# ife19_TS_BMS_v2_Eagle.net
KiCad netlist of a schematic drawn in EAGLE
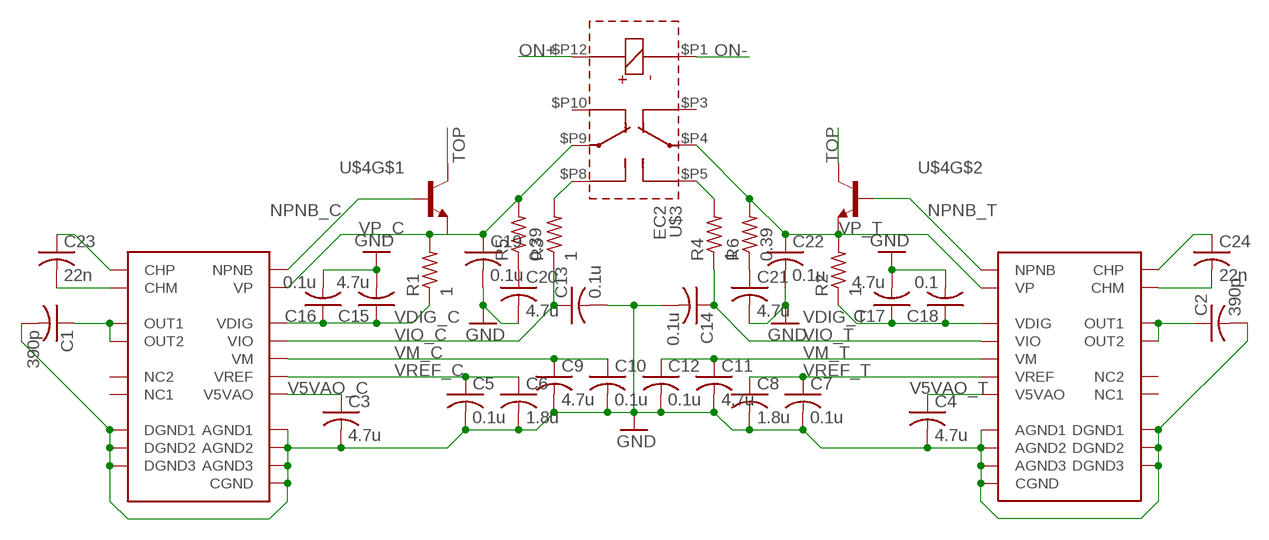
[diagram p0: schematic, sheet 1]
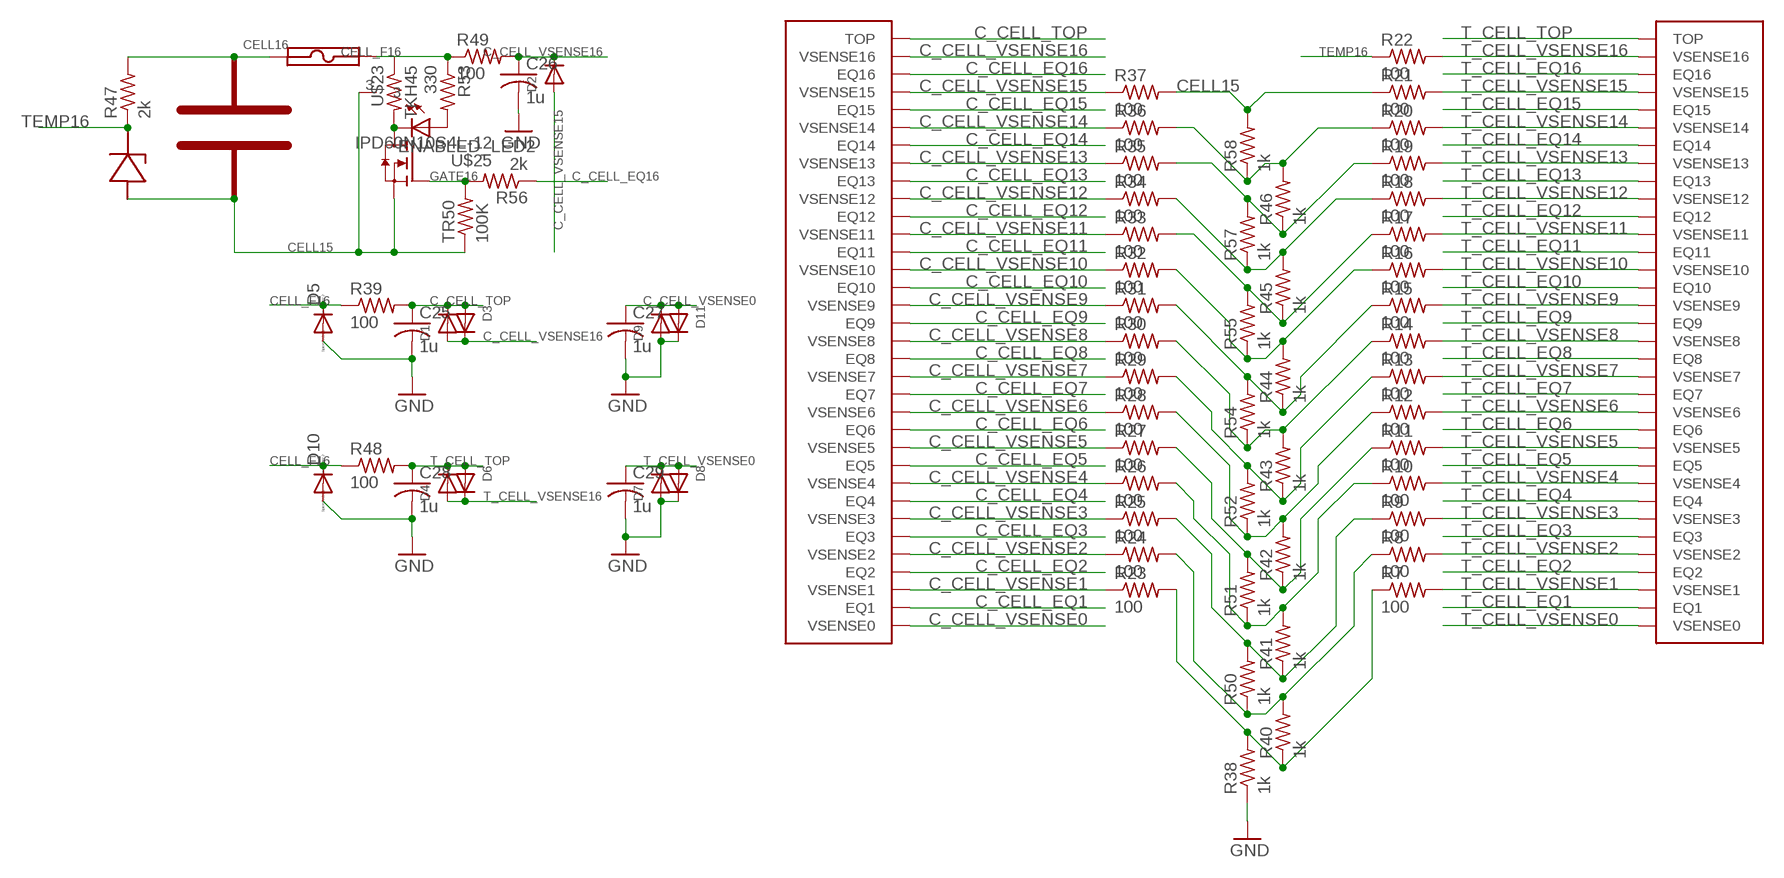
[diagram p1: schematic, sheet 2]
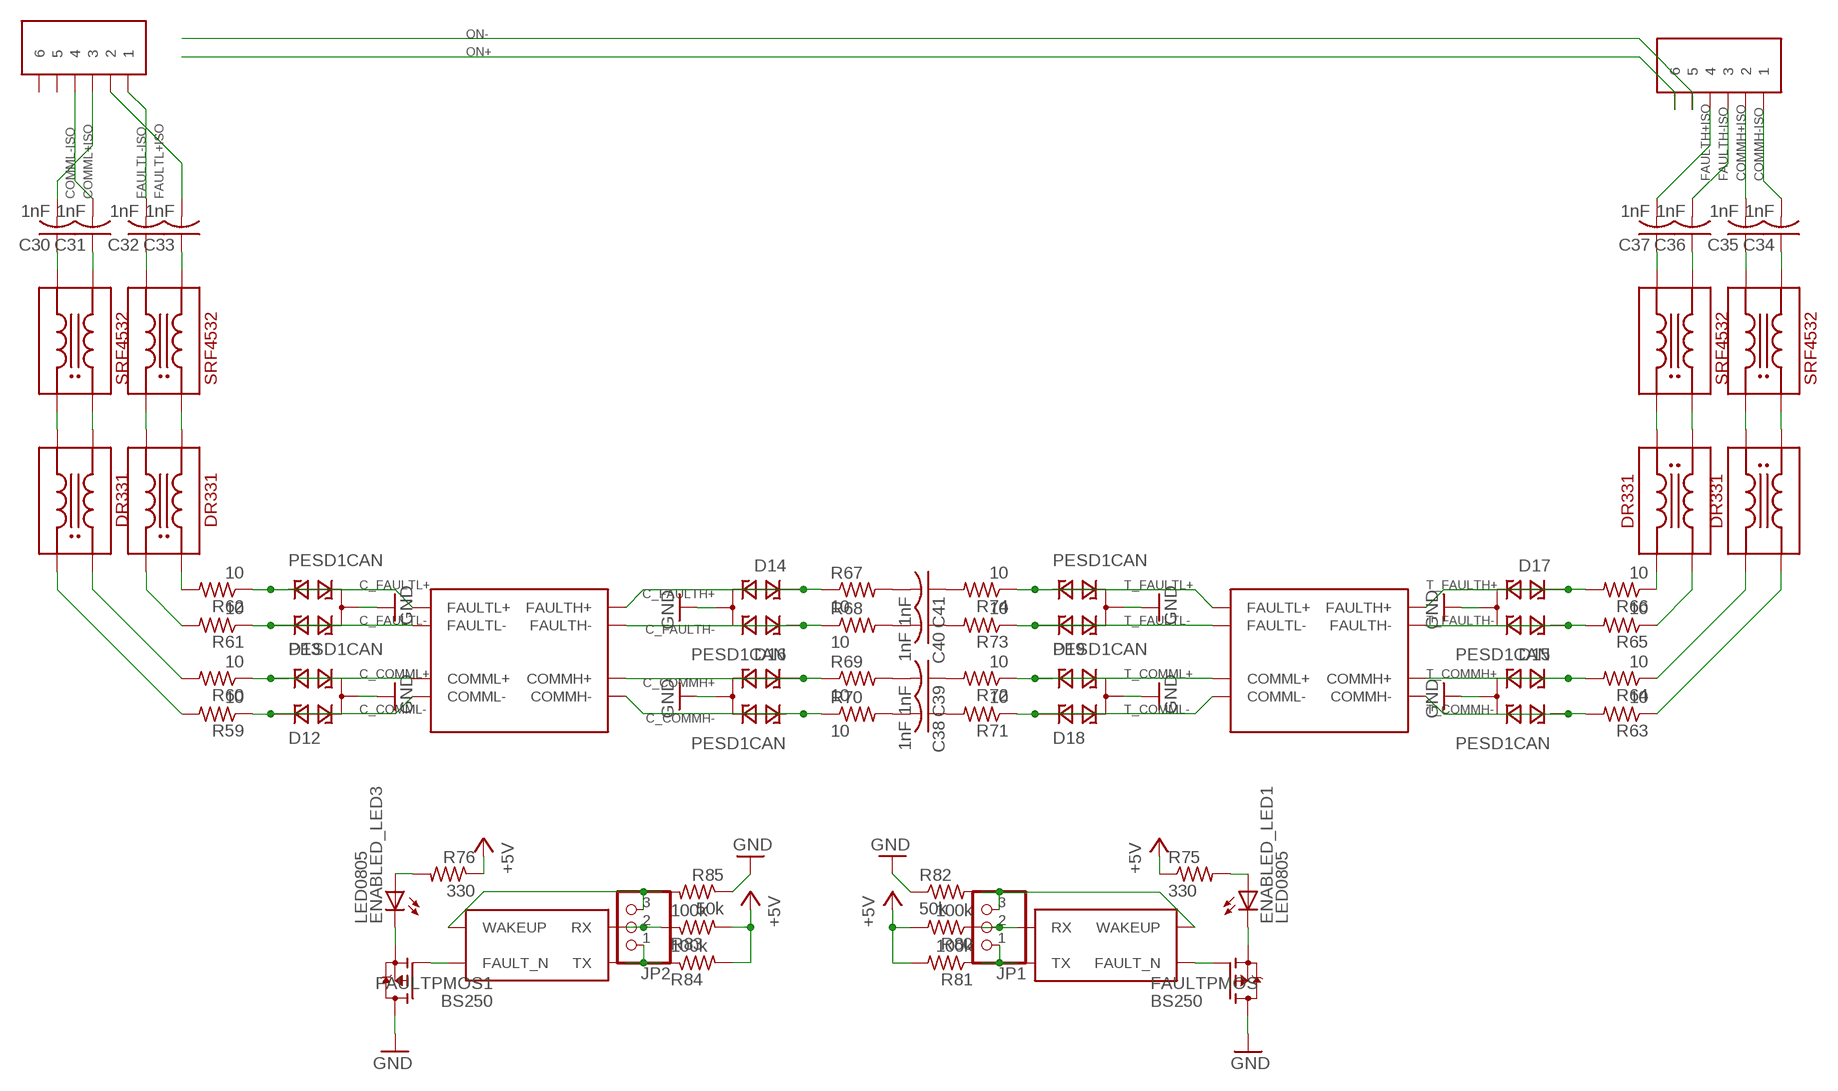
[diagram p2: schematic, sheet 3]
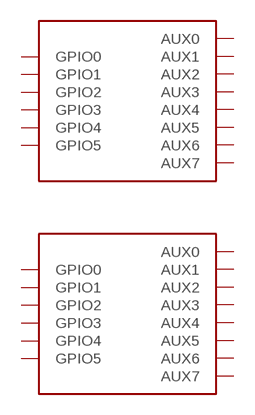
[diagram p3: schematic, sheet 4]

(export (version "E")
  (design (tool "Eeschema 10.0.6"))
  (components
    (comp (ref "C")
      (value "BQ76PL455A")
      (footprint "eagle-import:TQFP80")
      (libsource (lib "eagle-import") (part "BQ76PL455A"))
    )
    (comp (ref "C1")
      (value "390p")
      (footprint "eagle-import:C0603K")
      (libsource (lib "eagle-import") (part "C-USC0603K"))
    )
    (comp (ref "C2")
      (value "390p")
      (footprint "eagle-import:C0603K")
      (libsource (lib "eagle-import") (part "C-USC0603K"))
    )
    (comp (ref "C3")
      (value "4.7u")
      (footprint "eagle-import:C0603K")
      (libsource (lib "eagle-import") (part "C-USC0603K"))
    )
    (comp (ref "C4")
      (value "4.7u")
      (footprint "eagle-import:C0603K")
      (libsource (lib "eagle-import") (part "C-USC0603K"))
    )
    (comp (ref "C5")
      (value "0.1u")
      (footprint "eagle-import:C0603K")
      (libsource (lib "eagle-import") (part "C-USC0603K"))
    )
    (comp (ref "C6")
      (value "1.8u")
      (footprint "eagle-import:C0603K")
      (libsource (lib "eagle-import") (part "C-USC0603K"))
    )
    (comp (ref "C7")
      (value "0.1u")
      (footprint "eagle-import:C0603K")
      (libsource (lib "eagle-import") (part "C-USC0603K"))
    )
    (comp (ref "C8")
      (value "1.8u")
      (footprint "eagle-import:C0603K")
      (libsource (lib "eagle-import") (part "C-USC0603K"))
    )
    (comp (ref "C9")
      (value "4.7u")
      (footprint "eagle-import:C0603K")
      (libsource (lib "eagle-import") (part "C-USC0603K"))
    )
    (comp (ref "C10")
      (value "0.1u")
      (footprint "eagle-import:C0603K")
      (libsource (lib "eagle-import") (part "C-USC0603K"))
    )
    (comp (ref "C11")
      (value "4.7u")
      (footprint "eagle-import:C0603K")
      (libsource (lib "eagle-import") (part "C-USC0603K"))
    )
    (comp (ref "C12")
      (value "0.1u")
      (footprint "eagle-import:C0603K")
      (libsource (lib "eagle-import") (part "C-USC0603K"))
    )
    (comp (ref "C13")
      (value "0.1u")
      (footprint "eagle-import:C0603K")
      (libsource (lib "eagle-import") (part "C-USC0603K"))
    )
    (comp (ref "C14")
      (value "0.1u")
      (footprint "eagle-import:C0603K")
      (libsource (lib "eagle-import") (part "C-USC0603K"))
    )
    (comp (ref "C15")
      (value "4.7u")
      (footprint "eagle-import:C0603K")
      (libsource (lib "eagle-import") (part "C-USC0603K"))
    )
    (comp (ref "C16")
      (value "0.1u")
      (footprint "eagle-import:C0603K")
      (libsource (lib "eagle-import") (part "C-USC0603K"))
    )
    (comp (ref "C17")
      (value "4.7u")
      (footprint "eagle-import:C0603K")
      (libsource (lib "eagle-import") (part "C-USC0603K"))
    )
    (comp (ref "C18")
      (value "0.1")
      (footprint "eagle-import:C0603K")
      (libsource (lib "eagle-import") (part "C-USC0603K"))
    )
    (comp (ref "C19")
      (value "0.1u")
      (footprint "eagle-import:C0603K")
      (libsource (lib "eagle-import") (part "C-USC0603K"))
    )
    (comp (ref "C20")
      (value "4.7u")
      (footprint "eagle-import:C0603K")
      (libsource (lib "eagle-import") (part "C-USC0603K"))
    )
    (comp (ref "C21")
      (value "4.7u")
      (footprint "eagle-import:C0603K")
      (libsource (lib "eagle-import") (part "C-USC0603K"))
    )
    (comp (ref "C22")
      (value "0.1u")
      (footprint "eagle-import:C0603K")
      (libsource (lib "eagle-import") (part "C-USC0603K"))
    )
    (comp (ref "C23")
      (value "22n")
      (footprint "eagle-import:C0603")
      (libsource (lib "eagle-import") (part "C-USC0603"))
    )
    (comp (ref "C24")
      (value "22n")
      (footprint "eagle-import:C0603")
      (libsource (lib "eagle-import") (part "C-USC0603"))
    )
    (comp (ref "R1")
      (value "1")
      (footprint "eagle-import:R0603")
      (libsource (lib "eagle-import") (part "R-US_R0603"))
    )
    (comp (ref "R2")
      (value "1")
      (footprint "eagle-import:R0603")
      (libsource (lib "eagle-import") (part "R-US_R0603"))
    )
    (comp (ref "R3")
      (value "1")
      (footprint "eagle-import:R0603")
      (libsource (lib "eagle-import") (part "R-US_R0603"))
    )
    (comp (ref "R4")
      (value "1")
      (footprint "eagle-import:R0603")
      (libsource (lib "eagle-import") (part "R-US_R0603"))
    )
    (comp (ref "R5")
      (value "0.39")
      (footprint "eagle-import:R0603")
      (libsource (lib "eagle-import") (part "R-US_R0603"))
    )
    (comp (ref "R6")
      (value "0.39")
      (footprint "eagle-import:R0603")
      (libsource (lib "eagle-import") (part "R-US_R0603"))
    )
    (comp (ref "T")
      (value "BQ76PL455A")
      (footprint "eagle-import:TQFP80")
      (libsource (lib "eagle-import") (part "BQ76PL455A"))
    )
    (comp (ref "U$3")
      (value "EC2")
      (footprint "eagle-import:DPDT_2.54")
      (libsource (lib "eagle-import") (part "EC2"))
    )
    (comp (ref "U$4")
      (value "PHPT610030NK")
      (footprint "eagle-import:LFPAK56D")
      (libsource (lib "eagle-import") (part "PHPT610030NK"))
    )
    (comp (ref "C25")
      (value "1u")
      (footprint "eagle-import:C0603K")
      (libsource (lib "eagle-import") (part "C-USC0603K"))
    )
    (comp (ref "C26")
      (value "1u")
      (footprint "eagle-import:C0603K")
      (libsource (lib "eagle-import") (part "C-USC0603K"))
    )
    (comp (ref "C27")
      (value "1u")
      (footprint "eagle-import:C0603K")
      (libsource (lib "eagle-import") (part "C-USC0603K"))
    )
    (comp (ref "C28")
      (value "1u")
      (footprint "eagle-import:C0603K")
      (libsource (lib "eagle-import") (part "C-USC0603K"))
    )
    (comp (ref "C29")
      (value "1u")
      (footprint "eagle-import:C0603K")
      (libsource (lib "eagle-import") (part "C-USC0603K"))
    )
    (comp (ref "D1")
      (value "DIODESOD-123")
      (footprint "eagle-import:SOD-123")
      (libsource (lib "eagle-import") (part "DIODESOD-123"))
    )
    (comp (ref "D2")
      (value "DIODESOD-123")
      (footprint "eagle-import:SOD-123")
      (libsource (lib "eagle-import") (part "DIODESOD-123"))
    )
    (comp (ref "D3")
      (value "DIODESOD-123")
      (footprint "eagle-import:SOD-123")
      (libsource (lib "eagle-import") (part "DIODESOD-123"))
    )
    (comp (ref "D4")
      (value "DIODESOD-123")
      (footprint "eagle-import:SOD-123")
      (libsource (lib "eagle-import") (part "DIODESOD-123"))
    )
    (comp (ref "D5")
      (value "DIODE-DO214AC")
      (footprint "eagle-import:DO214AC")
      (libsource (lib "eagle-import") (part "DIODE-DO214AC"))
    )
    (comp (ref "D6")
      (value "DIODESOD-123")
      (footprint "eagle-import:SOD-123")
      (libsource (lib "eagle-import") (part "DIODESOD-123"))
    )
    (comp (ref "D7")
      (value "DIODESOD-123")
      (footprint "eagle-import:SOD-123")
      (libsource (lib "eagle-import") (part "DIODESOD-123"))
    )
    (comp (ref "D8")
      (value "DIODESOD-123")
      (footprint "eagle-import:SOD-123")
      (libsource (lib "eagle-import") (part "DIODESOD-123"))
    )
    (comp (ref "D9")
      (value "DIODESOD-123")
      (footprint "eagle-import:SOD-123")
      (libsource (lib "eagle-import") (part "DIODESOD-123"))
    )
    (comp (ref "D10")
      (value "DIODE-DO214AC")
      (footprint "eagle-import:DO214AC")
      (libsource (lib "eagle-import") (part "DIODE-DO214AC"))
    )
    (comp (ref "D11")
      (value "DIODESOD-123")
      (footprint "eagle-import:SOD-123")
      (libsource (lib "eagle-import") (part "DIODESOD-123"))
    )
    (comp (ref "ENABLED_LED2")
      (value "LEDCHIPLED_0603")
      (footprint "eagle-import:CHIPLED_0603")
      (libsource (lib "eagle-import") (part "LEDCHIPLED_0603"))
    )
    (comp (ref "R7")
      (value "100")
      (footprint "eagle-import:R0603")
      (libsource (lib "eagle-import") (part "R-US_R0603"))
    )
    (comp (ref "R8")
      (value "100")
      (footprint "eagle-import:R0603")
      (libsource (lib "eagle-import") (part "R-US_R0603"))
    )
    (comp (ref "R9")
      (value "100")
      (footprint "eagle-import:R0603")
      (libsource (lib "eagle-import") (part "R-US_R0603"))
    )
    (comp (ref "R10")
      (value "100")
      (footprint "eagle-import:R0603")
      (libsource (lib "eagle-import") (part "R-US_R0603"))
    )
    (comp (ref "R11")
      (value "100")
      (footprint "eagle-import:R0603")
      (libsource (lib "eagle-import") (part "R-US_R0603"))
    )
    (comp (ref "R12")
      (value "100")
      (footprint "eagle-import:R0603")
      (libsource (lib "eagle-import") (part "R-US_R0603"))
    )
    (comp (ref "R13")
      (value "100")
      (footprint "eagle-import:R0603")
      (libsource (lib "eagle-import") (part "R-US_R0603"))
    )
    (comp (ref "R14")
      (value "100")
      (footprint "eagle-import:R0603")
      (libsource (lib "eagle-import") (part "R-US_R0603"))
    )
    (comp (ref "R15")
      (value "100")
      (footprint "eagle-import:R0603")
      (libsource (lib "eagle-import") (part "R-US_R0603"))
    )
    (comp (ref "R16")
      (value "100")
      (footprint "eagle-import:R0603")
      (libsource (lib "eagle-import") (part "R-US_R0603"))
    )
    (comp (ref "R17")
      (value "100")
      (footprint "eagle-import:R0603")
      (libsource (lib "eagle-import") (part "R-US_R0603"))
    )
    (comp (ref "R18")
      (value "100")
      (footprint "eagle-import:R0603")
      (libsource (lib "eagle-import") (part "R-US_R0603"))
    )
    (comp (ref "R19")
      (value "100")
      (footprint "eagle-import:R0603")
      (libsource (lib "eagle-import") (part "R-US_R0603"))
    )
    (comp (ref "R20")
      (value "100")
      (footprint "eagle-import:R0603")
      (libsource (lib "eagle-import") (part "R-US_R0603"))
    )
    (comp (ref "R21")
      (value "100")
      (footprint "eagle-import:R0603")
      (libsource (lib "eagle-import") (part "R-US_R0603"))
    )
    (comp (ref "R22")
      (value "100")
      (footprint "eagle-import:R0603")
      (libsource (lib "eagle-import") (part "R-US_R0603"))
    )
    (comp (ref "R23")
      (value "100")
      (footprint "eagle-import:R0603")
      (libsource (lib "eagle-import") (part "R-US_R0603"))
    )
    (comp (ref "R24")
      (value "100")
      (footprint "eagle-import:R0603")
      (libsource (lib "eagle-import") (part "R-US_R0603"))
    )
    (comp (ref "R25")
      (value "100")
      (footprint "eagle-import:R0603")
      (libsource (lib "eagle-import") (part "R-US_R0603"))
    )
    (comp (ref "R26")
      (value "100")
      (footprint "eagle-import:R0603")
      (libsource (lib "eagle-import") (part "R-US_R0603"))
    )
    (comp (ref "R27")
      (value "100")
      (footprint "eagle-import:R0603")
      (libsource (lib "eagle-import") (part "R-US_R0603"))
    )
    (comp (ref "R28")
      (value "100")
      (footprint "eagle-import:R0603")
      (libsource (lib "eagle-import") (part "R-US_R0603"))
    )
    (comp (ref "R29")
      (value "100")
      (footprint "eagle-import:R0603")
      (libsource (lib "eagle-import") (part "R-US_R0603"))
    )
    (comp (ref "R30")
      (value "100")
      (footprint "eagle-import:R0603")
      (libsource (lib "eagle-import") (part "R-US_R0603"))
    )
    (comp (ref "R31")
      (value "100")
      (footprint "eagle-import:R0603")
      (libsource (lib "eagle-import") (part "R-US_R0603"))
    )
    (comp (ref "R32")
      (value "100")
      (footprint "eagle-import:R0603")
      (libsource (lib "eagle-import") (part "R-US_R0603"))
    )
    (comp (ref "R33")
      (value "100")
      (footprint "eagle-import:R0603")
      (libsource (lib "eagle-import") (part "R-US_R0603"))
    )
    (comp (ref "R34")
      (value "100")
      (footprint "eagle-import:R0603")
      (libsource (lib "eagle-import") (part "R-US_R0603"))
    )
    (comp (ref "R35")
      (value "100")
      (footprint "eagle-import:R0603")
      (libsource (lib "eagle-import") (part "R-US_R0603"))
    )
    (comp (ref "R36")
      (value "100")
      (footprint "eagle-import:R0603")
      (libsource (lib "eagle-import") (part "R-US_R0603"))
    )
    (comp (ref "R37")
      (value "100")
      (footprint "eagle-import:R0603")
      (libsource (lib "eagle-import") (part "R-US_R0603"))
    )
    (comp (ref "R38")
      (value "1k")
      (footprint "eagle-import:R0603")
      (libsource (lib "eagle-import") (part "R-US_R0603"))
    )
    (comp (ref "R39")
      (value "100")
      (footprint "eagle-import:R0603")
      (libsource (lib "eagle-import") (part "R-US_R0603"))
    )
    (comp (ref "R40")
      (value "1k")
      (footprint "eagle-import:R0603")
      (libsource (lib "eagle-import") (part "R-US_R0603"))
    )
    (comp (ref "R41")
      (value "1k")
      (footprint "eagle-import:R0603")
      (libsource (lib "eagle-import") (part "R-US_R0603"))
    )
    (comp (ref "R42")
      (value "1k")
      (footprint "eagle-import:R0603")
      (libsource (lib "eagle-import") (part "R-US_R0603"))
    )
    (comp (ref "R43")
      (value "1k")
      (footprint "eagle-import:R0603")
      (libsource (lib "eagle-import") (part "R-US_R0603"))
    )
    (comp (ref "R44")
      (value "1k")
      (footprint "eagle-import:R0603")
      (libsource (lib "eagle-import") (part "R-US_R0603"))
    )
    (comp (ref "R45")
      (value "1k")
      (footprint "eagle-import:R0603")
      (libsource (lib "eagle-import") (part "R-US_R0603"))
    )
    (comp (ref "R46")
      (value "1k")
      (footprint "eagle-import:R0603")
      (libsource (lib "eagle-import") (part "R-US_R0603"))
    )
    (comp (ref "R47")
      (value "2k")
      (footprint "eagle-import:R0603")
      (libsource (lib "eagle-import") (part "R-US_R0603"))
    )
    (comp (ref "R48")
      (value "100")
      (footprint "eagle-import:R0603")
      (libsource (lib "eagle-import") (part "R-US_R0603"))
    )
    (comp (ref "R49")
      (value "100")
      (footprint "eagle-import:R0603")
      (libsource (lib "eagle-import") (part "R-US_R0603"))
    )
    (comp (ref "R50")
      (value "1k")
      (footprint "eagle-import:R0603")
      (libsource (lib "eagle-import") (part "R-US_R0603"))
    )
    (comp (ref "R51")
      (value "1k")
      (footprint "eagle-import:R0603")
      (libsource (lib "eagle-import") (part "R-US_R0603"))
    )
    (comp (ref "R52")
      (value "1k")
      (footprint "eagle-import:R0603")
      (libsource (lib "eagle-import") (part "R-US_R0603"))
    )
    (comp (ref "R53")
      (value "330")
      (footprint "eagle-import:R0603")
      (libsource (lib "eagle-import") (part "R-US_R0603"))
    )
    (comp (ref "R54")
      (value "1k")
      (footprint "eagle-import:R0603")
      (libsource (lib "eagle-import") (part "R-US_R0603"))
    )
    (comp (ref "R55")
      (value "1k")
      (footprint "eagle-import:R0603")
      (libsource (lib "eagle-import") (part "R-US_R0603"))
    )
    (comp (ref "R56")
      (value "2k")
      (footprint "eagle-import:R0603")
      (libsource (lib "eagle-import") (part "R-US_R0603"))
    )
    (comp (ref "R57")
      (value "1k")
      (footprint "eagle-import:R0603")
      (libsource (lib "eagle-import") (part "R-US_R0603"))
    )
    (comp (ref "R58")
      (value "1k")
      (footprint "eagle-import:R0603")
      (libsource (lib "eagle-import") (part "R-US_R0603"))
    )
    (comp (ref "TR50")
      (value "100K")
      (footprint "eagle-import:R0603")
      (libsource (lib "eagle-import") (part "R-US_R0603"))
    )
    (comp (ref "U$1")
      (value "LI6PT")
      (footprint "eagle-import:6PT")
      (libsource (lib "eagle-import") (part "LI6PT"))
    )
    (comp (ref "U$22")
      (value "SF-0603FP")
      (footprint "eagle-import:0603")
      (libsource (lib "eagle-import") (part "SF-0603FP"))
    )
    (comp (ref "U$23")
      (value "TKH45")
      (footprint "eagle-import:TO252-TKH-45")
      (libsource (lib "eagle-import") (part "TKH45"))
    )
    (comp (ref "U$25")
      (value "IPD60N10S4L-12")
      (footprint "eagle-import:TO252")
      (libsource (lib "eagle-import") (part "IPD60N10S4L-12"))
    )
    (comp (ref "C30")
      (value "1nF")
      (footprint "eagle-import:C0805")
      (libsource (lib "eagle-import") (part "C-USC0805"))
    )
    (comp (ref "C31")
      (value "1nF")
      (footprint "eagle-import:C0805")
      (libsource (lib "eagle-import") (part "C-USC0805"))
    )
    (comp (ref "C32")
      (value "1nF")
      (footprint "eagle-import:C0805")
      (libsource (lib "eagle-import") (part "C-USC0805"))
    )
    (comp (ref "C33")
      (value "1nF")
      (footprint "eagle-import:C0805")
      (libsource (lib "eagle-import") (part "C-USC0805"))
    )
    (comp (ref "C34")
      (value "1nF")
      (footprint "eagle-import:C0805")
      (libsource (lib "eagle-import") (part "C-USC0805"))
    )
    (comp (ref "C35")
      (value "1nF")
      (footprint "eagle-import:C0805")
      (libsource (lib "eagle-import") (part "C-USC0805"))
    )
    (comp (ref "C36")
      (value "1nF")
      (footprint "eagle-import:C0805")
      (libsource (lib "eagle-import") (part "C-USC0805"))
    )
    (comp (ref "C37")
      (value "1nF")
      (footprint "eagle-import:C0805")
      (libsource (lib "eagle-import") (part "C-USC0805"))
    )
    (comp (ref "C38")
      (value "1nF")
      (footprint "eagle-import:C0805")
      (libsource (lib "eagle-import") (part "C-USC0805"))
    )
    (comp (ref "C39")
      (value "1nF")
      (footprint "eagle-import:C0805")
      (libsource (lib "eagle-import") (part "C-USC0805"))
    )
    (comp (ref "C40")
      (value "1nF")
      (footprint "eagle-import:C0805")
      (libsource (lib "eagle-import") (part "C-USC0805"))
    )
    (comp (ref "C41")
      (value "1nF")
      (footprint "eagle-import:C0805")
      (libsource (lib "eagle-import") (part "C-USC0805"))
    )
    (comp (ref "D12")
      (value "PESD1CAN")
      (footprint "eagle-import:SOT23")
      (libsource (lib "eagle-import") (part "PESD1CAN"))
    )
    (comp (ref "D13")
      (value "PESD1CAN")
      (footprint "eagle-import:SOT23")
      (libsource (lib "eagle-import") (part "PESD1CAN"))
    )
    (comp (ref "D14")
      (value "PESD1CAN")
      (footprint "eagle-import:SOT23")
      (libsource (lib "eagle-import") (part "PESD1CAN"))
    )
    (comp (ref "D15")
      (value "PESD1CAN")
      (footprint "eagle-import:SOT23")
      (libsource (lib "eagle-import") (part "PESD1CAN"))
    )
    (comp (ref "D16")
      (value "PESD1CAN")
      (footprint "eagle-import:SOT23")
      (libsource (lib "eagle-import") (part "PESD1CAN"))
    )
    (comp (ref "D17")
      (value "PESD1CAN")
      (footprint "eagle-import:SOT23")
      (libsource (lib "eagle-import") (part "PESD1CAN"))
    )
    (comp (ref "D18")
      (value "PESD1CAN")
      (footprint "eagle-import:SOT23")
      (libsource (lib "eagle-import") (part "PESD1CAN"))
    )
    (comp (ref "D19")
      (value "PESD1CAN")
      (footprint "eagle-import:SOT23")
      (libsource (lib "eagle-import") (part "PESD1CAN"))
    )
    (comp (ref "ENABLED_LED1")
      (value "LED0805")
      (footprint "eagle-import:LED0805")
      (libsource (lib "eagle-import") (part "LED0805"))
    )
    (comp (ref "ENABLED_LED3")
      (value "LED0805")
      (footprint "eagle-import:LED0805")
      (libsource (lib "eagle-import") (part "LED0805"))
    )
    (comp (ref "FAULTPMOS")
      (value "BS250")
      (footprint "eagle-import:SOT23")
      (libsource (lib "eagle-import") (part "BS250"))
    )
    (comp (ref "FAULTPMOS1")
      (value "BS250")
      (footprint "eagle-import:SOT23")
      (libsource (lib "eagle-import") (part "BS250"))
    )
    (comp (ref "JP1")
      (value "PINHD-1X3CB")
      (footprint "eagle-import:1X03-CLEANBIG")
      (libsource (lib "eagle-import") (part "PINHD-1X3CB"))
    )
    (comp (ref "JP2")
      (value "PINHD-1X3CB")
      (footprint "eagle-import:1X03-CLEANBIG")
      (libsource (lib "eagle-import") (part "PINHD-1X3CB"))
    )
    (comp (ref "R59")
      (value "10")
      (footprint "eagle-import:R0805")
      (libsource (lib "eagle-import") (part "R-US_R0805"))
    )
    (comp (ref "R60")
      (value "10")
      (footprint "eagle-import:R0805")
      (libsource (lib "eagle-import") (part "R-US_R0805"))
    )
    (comp (ref "R61")
      (value "10")
      (footprint "eagle-import:R0805")
      (libsource (lib "eagle-import") (part "R-US_R0805"))
    )
    (comp (ref "R62")
      (value "10")
      (footprint "eagle-import:R0805")
      (libsource (lib "eagle-import") (part "R-US_R0805"))
    )
    (comp (ref "R63")
      (value "10")
      (footprint "eagle-import:R0805")
      (libsource (lib "eagle-import") (part "R-US_R0805"))
    )
    (comp (ref "R64")
      (value "10")
      (footprint "eagle-import:R0805")
      (libsource (lib "eagle-import") (part "R-US_R0805"))
    )
    (comp (ref "R65")
      (value "10")
      (footprint "eagle-import:R0805")
      (libsource (lib "eagle-import") (part "R-US_R0805"))
    )
    (comp (ref "R66")
      (value "10")
      (footprint "eagle-import:R0805")
      (libsource (lib "eagle-import") (part "R-US_R0805"))
    )
    (comp (ref "R67")
      (value "10")
      (footprint "eagle-import:R0805")
      (libsource (lib "eagle-import") (part "R-US_R0805"))
    )
    (comp (ref "R68")
      (value "10")
      (footprint "eagle-import:R0805")
      (libsource (lib "eagle-import") (part "R-US_R0805"))
    )
    (comp (ref "R69")
      (value "10")
      (footprint "eagle-import:R0805")
      (libsource (lib "eagle-import") (part "R-US_R0805"))
    )
    (comp (ref "R70")
      (value "10")
      (footprint "eagle-import:R0805")
      (libsource (lib "eagle-import") (part "R-US_R0805"))
    )
    (comp (ref "R71")
      (value "10")
      (footprint "eagle-import:R0805")
      (libsource (lib "eagle-import") (part "R-US_R0805"))
    )
    (comp (ref "R72")
      (value "10")
      (footprint "eagle-import:R0805")
      (libsource (lib "eagle-import") (part "R-US_R0805"))
    )
    (comp (ref "R73")
      (value "10")
      (footprint "eagle-import:R0805")
      (libsource (lib "eagle-import") (part "R-US_R0805"))
    )
    (comp (ref "R74")
      (value "10")
      (footprint "eagle-import:R0805")
      (libsource (lib "eagle-import") (part "R-US_R0805"))
    )
    (comp (ref "R75")
      (value "330")
      (footprint "eagle-import:R0805")
      (libsource (lib "eagle-import") (part "R-US_R0805"))
    )
    (comp (ref "R76")
      (value "330")
      (footprint "eagle-import:R0805")
      (libsource (lib "eagle-import") (part "R-US_R0805"))
    )
    (comp (ref "R80")
      (value "100k")
      (footprint "eagle-import:R0805")
      (libsource (lib "eagle-import") (part "R-US_R0805"))
    )
    (comp (ref "R81")
      (value "100k")
      (footprint "eagle-import:R0805")
      (libsource (lib "eagle-import") (part "R-US_R0805"))
    )
    (comp (ref "R82")
      (value "50k")
      (footprint "eagle-import:R0805")
      (libsource (lib "eagle-import") (part "R-US_R0805"))
    )
    (comp (ref "R83")
      (value "100k")
      (footprint "eagle-import:R0805")
      (libsource (lib "eagle-import") (part "R-US_R0805"))
    )
    (comp (ref "R84")
      (value "100k")
      (footprint "eagle-import:R0805")
      (libsource (lib "eagle-import") (part "R-US_R0805"))
    )
    (comp (ref "R85")
      (value "50k")
      (footprint "eagle-import:R0805")
      (libsource (lib "eagle-import") (part "R-US_R0805"))
    )
    (comp (ref "U$2")
      (value "SRF5432")
      (footprint "eagle-import:SRF5432")
      (libsource (lib "eagle-import") (part "SRF5432"))
    )
    (comp (ref "U$5")
      (value "MICROFIT3.0-3P")
      (footprint "eagle-import:6POS-3MM")
      (libsource (lib "eagle-import") (part "MICROFIT3.0-3P"))
    )
    (comp (ref "U$6")
      (value "SRF5432")
      (footprint "eagle-import:SRF5432")
      (libsource (lib "eagle-import") (part "SRF5432"))
    )
    (comp (ref "U$7")
      (value "MICROFIT3.0-3P")
      (footprint "eagle-import:6POS-3MM")
      (libsource (lib "eagle-import") (part "MICROFIT3.0-3P"))
    )
    (comp (ref "U$8")
      (value "SRF5432")
      (footprint "eagle-import:SRF5432")
      (libsource (lib "eagle-import") (part "SRF5432"))
    )
    (comp (ref "U$9")
      (value "SRF5432")
      (footprint "eagle-import:SRF5432")
      (libsource (lib "eagle-import") (part "SRF5432"))
    )
    (comp (ref "U$10")
      (value "DR331")
      (footprint "eagle-import:DR331")
      (libsource (lib "eagle-import") (part "DR331"))
    )
    (comp (ref "U$12")
      (value "DR331")
      (footprint "eagle-import:DR331")
      (libsource (lib "eagle-import") (part "DR331"))
    )
    (comp (ref "U$14")
      (value "DR331")
      (footprint "eagle-import:DR331")
      (libsource (lib "eagle-import") (part "DR331"))
    )
    (comp (ref "U$16")
      (value "DR331")
      (footprint "eagle-import:DR331")
      (libsource (lib "eagle-import") (part "DR331"))
    )
  )
  (nets
    (net (code "1") (name "+5V") (class "Default")
      (node (ref "R75") (pin "1") (pinfunction "1_1") (pintype "passive"))
      (node (ref "R76") (pin "1") (pinfunction "1_1") (pintype "passive"))
      (node (ref "R80") (pin "2") (pinfunction "2_2") (pintype "passive"))
      (node (ref "R81") (pin "2") (pinfunction "2_2") (pintype "passive"))
      (node (ref "R83") (pin "2") (pinfunction "2_2") (pintype "passive"))
      (node (ref "R84") (pin "2") (pinfunction "2_2") (pintype "passive"))
    )
    (net (code "2") (name "CELL15") (class "Default")
      (node (ref "R21") (pin "1") (pinfunction "1_1") (pintype "passive"))
      (node (ref "R37") (pin "2") (pinfunction "2_2") (pintype "passive"))
      (node (ref "R58") (pin "2") (pinfunction "2_2") (pintype "passive"))
      (node (ref "TR50") (pin "1") (pinfunction "1_1") (pintype "passive"))
      (node (ref "U$1") (pin "1") (pinfunction "TEMP-_1") (pintype "bidirectional"))
      (node (ref "U$1") (pin "CELLH-") (pinfunction "CELL-_CELLH-") (pintype "bidirectional"))
      (node (ref "U$1") (pin "CELLP-") (pinfunction "CELL-_CELLP-") (pintype "bidirectional"))
      (node (ref "U$23") (pin "3") (pinfunction "3_3") (pintype "passive"))
      (node (ref "U$25") (pin "3") (pinfunction "S_3") (pintype "passive"))
    )
    (net (code "3") (name "CELL16") (class "Default")
      (node (ref "R47") (pin "2") (pinfunction "2_2") (pintype "passive"))
      (node (ref "U$1") (pin "CELLH+") (pinfunction "CELL+_CELLH+") (pintype "bidirectional"))
      (node (ref "U$1") (pin "CELLP+") (pinfunction "CELL+_CELLP+") (pintype "bidirectional"))
      (node (ref "U$22") (pin "1") (pinfunction "P$1_1") (pintype "bidirectional"))
    )
    (net (code "4") (name "CELL_F16") (class "Default")
      (node (ref "D10") (pin "C") (pinfunction "C_C") (pintype "passive"))
      (node (ref "D5") (pin "C") (pinfunction "C_C") (pintype "passive"))
      (node (ref "R39") (pin "1") (pinfunction "1_1") (pintype "passive"))
      (node (ref "R48") (pin "1") (pinfunction "1_1") (pintype "passive"))
      (node (ref "R49") (pin "1") (pinfunction "1_1") (pintype "passive"))
      (node (ref "R53") (pin "1") (pinfunction "1_1") (pintype "passive"))
      (node (ref "U$22") (pin "2") (pinfunction "P$2_2") (pintype "bidirectional"))
      (node (ref "U$23") (pin "1") (pinfunction "1_1") (pintype "passive"))
    )
    (net (code "5") (name "COMMH+ISO") (class "Default")
      (node (ref "C35") (pin "2") (pinfunction "2_2") (pintype "passive"))
      (node (ref "U$7") (pin "P$2") (pinfunction "2_P$2") (pintype "bidirectional"))
    )
    (net (code "6") (name "COMMH-ISO") (class "Default")
      (node (ref "C34") (pin "2") (pinfunction "2_2") (pintype "passive"))
      (node (ref "U$7") (pin "P$1") (pinfunction "1_P$1") (pintype "bidirectional"))
    )
    (net (code "7") (name "COMML+ISO") (class "Default")
      (node (ref "C31") (pin "2") (pinfunction "2_2") (pintype "passive"))
      (node (ref "U$5") (pin "P$4") (pinfunction "4_P$4") (pintype "bidirectional"))
    )
    (net (code "8") (name "COMML-ISO") (class "Default")
      (node (ref "C30") (pin "2") (pinfunction "2_2") (pintype "passive"))
      (node (ref "U$5") (pin "P$3") (pinfunction "3_P$3") (pintype "bidirectional"))
    )
    (net (code "9") (name "C_CELL_EQ1") (class "Default")
      (node (ref "C") (pin "28") (pinfunction "EQ1_28") (pintype "bidirectional"))
    )
    (net (code "10") (name "C_CELL_EQ2") (class "Default")
      (node (ref "C") (pin "26") (pinfunction "EQ2_26") (pintype "bidirectional"))
    )
    (net (code "11") (name "C_CELL_EQ3") (class "Default")
      (node (ref "C") (pin "24") (pinfunction "EQ3_24") (pintype "bidirectional"))
    )
    (net (code "12") (name "C_CELL_EQ4") (class "Default")
      (node (ref "C") (pin "22") (pinfunction "EQ4_22") (pintype "bidirectional"))
    )
    (net (code "13") (name "C_CELL_EQ5") (class "Default")
      (node (ref "C") (pin "20") (pinfunction "EQ5_20") (pintype "bidirectional"))
    )
    (net (code "14") (name "C_CELL_EQ6") (class "Default")
      (node (ref "C") (pin "18") (pinfunction "EQ6_18") (pintype "bidirectional"))
    )
    (net (code "15") (name "C_CELL_EQ7") (class "Default")
      (node (ref "C") (pin "16") (pinfunction "EQ7_16") (pintype "bidirectional"))
    )
    (net (code "16") (name "C_CELL_EQ8") (class "Default")
      (node (ref "C") (pin "14") (pinfunction "EQ8_14") (pintype "bidirectional"))
    )
    (net (code "17") (name "C_CELL_EQ9") (class "Default")
      (node (ref "C") (pin "12") (pinfunction "EQ9_12") (pintype "bidirectional"))
    )
    (net (code "18") (name "C_CELL_EQ10") (class "Default")
      (node (ref "C") (pin "10") (pinfunction "EQ10_10") (pintype "bidirectional"))
    )
    (net (code "19") (name "C_CELL_EQ11") (class "Default")
      (node (ref "C") (pin "8") (pinfunction "EQ11_8") (pintype "bidirectional"))
    )
    (net (code "20") (name "C_CELL_EQ12") (class "Default")
      (node (ref "C") (pin "6") (pinfunction "EQ12_6") (pintype "bidirectional"))
    )
    (net (code "21") (name "C_CELL_EQ13") (class "Default")
      (node (ref "C") (pin "4") (pinfunction "EQ13_4") (pintype "bidirectional"))
    )
    (net (code "22") (name "C_CELL_EQ14") (class "Default")
      (node (ref "C") (pin "2") (pinfunction "EQ14_2") (pintype "bidirectional"))
    )
    (net (code "23") (name "C_CELL_EQ15") (class "Default")
      (node (ref "C") (pin "80") (pinfunction "EQ15_80") (pintype "bidirectional"))
    )
    (net (code "24") (name "C_CELL_EQ16") (class "Default")
      (node (ref "C") (pin "78") (pinfunction "EQ16_78") (pintype "bidirectional"))
      (node (ref "R56") (pin "1") (pinfunction "1_1") (pintype "passive"))
    )
    (net (code "25") (name "C_CELL_TOP") (class "Default")
      (node (ref "C") (pin "76") (pinfunction "TOP_76") (pintype "bidirectional"))
      (node (ref "C25") (pin "1") (pinfunction "1_1") (pintype "passive"))
      (node (ref "D1") (pin "C") (pinfunction "C_C") (pintype "passive"))
      (node (ref "D3") (pin "A") (pinfunction "A_A") (pintype "passive"))
      (node (ref "R39") (pin "2") (pinfunction "2_2") (pintype "passive"))
    )
    (net (code "26") (name "C_CELL_VSENSE0") (class "Default")
      (node (ref "C") (pin "29") (pinfunction "VSENSE0_29") (pintype "bidirectional"))
      (node (ref "C27") (pin "1") (pinfunction "1_1") (pintype "passive"))
      (node (ref "D11") (pin "A") (pinfunction "A_A") (pintype "passive"))
      (node (ref "D9") (pin "C") (pinfunction "C_C") (pintype "passive"))
    )
    (net (code "27") (name "C_CELL_VSENSE1") (class "Default")
      (node (ref "C") (pin "27") (pinfunction "VSENSE1_27") (pintype "bidirectional"))
      (node (ref "R23") (pin "1") (pinfunction "1_1") (pintype "passive"))
    )
    (net (code "28") (name "C_CELL_VSENSE2") (class "Default")
      (node (ref "C") (pin "25") (pinfunction "VSENSE2_25") (pintype "bidirectional"))
      (node (ref "R24") (pin "1") (pinfunction "1_1") (pintype "passive"))
    )
    (net (code "29") (name "C_CELL_VSENSE3") (class "Default")
      (node (ref "C") (pin "23") (pinfunction "VSENSE3_23") (pintype "bidirectional"))
      (node (ref "R25") (pin "1") (pinfunction "1_1") (pintype "passive"))
    )
    (net (code "30") (name "C_CELL_VSENSE4") (class "Default")
      (node (ref "C") (pin "21") (pinfunction "VSENSE4_21") (pintype "bidirectional"))
      (node (ref "R26") (pin "1") (pinfunction "1_1") (pintype "passive"))
    )
    (net (code "31") (name "C_CELL_VSENSE5") (class "Default")
      (node (ref "C") (pin "19") (pinfunction "VSENSE5_19") (pintype "bidirectional"))
      (node (ref "R27") (pin "1") (pinfunction "1_1") (pintype "passive"))
    )
    (net (code "32") (name "C_CELL_VSENSE6") (class "Default")
      (node (ref "C") (pin "17") (pinfunction "VSENSE6_17") (pintype "bidirectional"))
      (node (ref "R28") (pin "1") (pinfunction "1_1") (pintype "passive"))
    )
    (net (code "33") (name "C_CELL_VSENSE7") (class "Default")
      (node (ref "C") (pin "15") (pinfunction "VSENSE7_15") (pintype "bidirectional"))
      (node (ref "R29") (pin "1") (pinfunction "1_1") (pintype "passive"))
    )
    (net (code "34") (name "C_CELL_VSENSE8") (class "Default")
      (node (ref "C") (pin "13") (pinfunction "VSENSE8_13") (pintype "bidirectional"))
      (node (ref "R30") (pin "1") (pinfunction "1_1") (pintype "passive"))
    )
    (net (code "35") (name "C_CELL_VSENSE9") (class "Default")
      (node (ref "C") (pin "11") (pinfunction "VSENSE9_11") (pintype "bidirectional"))
      (node (ref "R31") (pin "1") (pinfunction "1_1") (pintype "passive"))
    )
    (net (code "36") (name "C_CELL_VSENSE10") (class "Default")
      (node (ref "C") (pin "9") (pinfunction "VSENSE10_9") (pintype "bidirectional"))
      (node (ref "R32") (pin "1") (pinfunction "1_1") (pintype "passive"))
    )
    (net (code "37") (name "C_CELL_VSENSE11") (class "Default")
      (node (ref "C") (pin "7") (pinfunction "VSENSE11_7") (pintype "bidirectional"))
      (node (ref "R33") (pin "1") (pinfunction "1_1") (pintype "passive"))
    )
    (net (code "38") (name "C_CELL_VSENSE12") (class "Default")
      (node (ref "C") (pin "5") (pinfunction "VSENSE12_5") (pintype "bidirectional"))
      (node (ref "R34") (pin "1") (pinfunction "1_1") (pintype "passive"))
    )
    (net (code "39") (name "C_CELL_VSENSE13") (class "Default")
      (node (ref "C") (pin "3") (pinfunction "VSENSE13_3") (pintype "bidirectional"))
      (node (ref "R35") (pin "1") (pinfunction "1_1") (pintype "passive"))
    )
    (net (code "40") (name "C_CELL_VSENSE14") (class "Default")
      (node (ref "C") (pin "1") (pinfunction "VSENSE14_1") (pintype "bidirectional"))
      (node (ref "R36") (pin "1") (pinfunction "1_1") (pintype "passive"))
    )
    (net (code "41") (name "C_CELL_VSENSE15") (class "Default")
      (node (ref "C") (pin "79") (pinfunction "VSENSE15_79") (pintype "bidirectional"))
      (node (ref "D2") (pin "A") (pinfunction "A_A") (pintype "passive"))
      (node (ref "R37") (pin "1") (pinfunction "1_1") (pintype "passive"))
    )
    (net (code "42") (name "C_CELL_VSENSE16") (class "Default")
      (node (ref "C") (pin "77") (pinfunction "VSENSE16_77") (pintype "bidirectional"))
      (node (ref "C26") (pin "1") (pinfunction "1_1") (pintype "passive"))
      (node (ref "D1") (pin "A") (pinfunction "A_A") (pintype "passive"))
      (node (ref "D2") (pin "C") (pinfunction "C_C") (pintype "passive"))
      (node (ref "D3") (pin "C") (pinfunction "C_C") (pintype "passive"))
      (node (ref "R49") (pin "2") (pinfunction "2_2") (pintype "passive"))
    )
    (net (code "43") (name "C_COMMH+") (class "Default")
      (node (ref "C") (pin "55") (pinfunction "COMMH+_55") (pintype "bidirectional"))
      (node (ref "D16") (pin "1") (pinfunction "1_1") (pintype "passive"))
      (node (ref "R69") (pin "1") (pinfunction "1_1") (pintype "passive"))
    )
    (net (code "44") (name "C_COMMH-") (class "Default")
      (node (ref "C") (pin "54") (pinfunction "COMMH-_54") (pintype "bidirectional"))
      (node (ref "D16") (pin "2") (pinfunction "2_2") (pintype "passive"))
      (node (ref "R70") (pin "1") (pinfunction "1_1") (pintype "passive"))
    )
    (net (code "45") (name "C_COMML+") (class "Default")
      (node (ref "C") (pin "52") (pinfunction "COMML+_52") (pintype "bidirectional"))
      (node (ref "D12") (pin "2") (pinfunction "2_2") (pintype "passive"))
      (node (ref "R60") (pin "1") (pinfunction "1_1") (pintype "passive"))
    )
    (net (code "46") (name "C_COMML-") (class "Default")
      (node (ref "C") (pin "53") (pinfunction "COMML-_53") (pintype "bidirectional"))
      (node (ref "D12") (pin "1") (pinfunction "1_1") (pintype "passive"))
      (node (ref "R59") (pin "1") (pinfunction "1_1") (pintype "passive"))
    )
    (net (code "47") (name "C_FAULTH+") (class "Default")
      (node (ref "C") (pin "57") (pinfunction "FAULTH+_57") (pintype "bidirectional"))
      (node (ref "D14") (pin "1") (pinfunction "1_1") (pintype "passive"))
      (node (ref "R67") (pin "1") (pinfunction "1_1") (pintype "passive"))
    )
    (net (code "48") (name "C_FAULTH-") (class "Default")
      (node (ref "C") (pin "56") (pinfunction "FAULTH-_56") (pintype "bidirectional"))
      (node (ref "D14") (pin "2") (pinfunction "2_2") (pintype "passive"))
      (node (ref "R68") (pin "1") (pinfunction "1_1") (pintype "passive"))
    )
    (net (code "49") (name "C_FAULTL+") (class "Default")
      (node (ref "C") (pin "50") (pinfunction "FAULTL+_50") (pintype "bidirectional"))
      (node (ref "D13") (pin "2") (pinfunction "2_2") (pintype "passive"))
      (node (ref "R62") (pin "1") (pinfunction "1_1") (pintype "passive"))
    )
    (net (code "50") (name "C_FAULTL-") (class "Default")
      (node (ref "C") (pin "51") (pinfunction "FAULTL-_51") (pintype "bidirectional"))
      (node (ref "D13") (pin "1") (pinfunction "1_1") (pintype "passive"))
      (node (ref "R61") (pin "1") (pinfunction "1_1") (pintype "passive"))
    )
    (net (code "51") (name "FAULTH+ISO") (class "Default")
      (node (ref "C37") (pin "2") (pinfunction "2_2") (pintype "passive"))
      (node (ref "U$7") (pin "P$4") (pinfunction "4_P$4") (pintype "bidirectional"))
    )
    (net (code "52") (name "FAULTH-ISO") (class "Default")
      (node (ref "C36") (pin "2") (pinfunction "2_2") (pintype "passive"))
      (node (ref "U$7") (pin "P$3") (pinfunction "3_P$3") (pintype "bidirectional"))
    )
    (net (code "53") (name "FAULTL+ISO") (class "Default")
      (node (ref "C33") (pin "2") (pinfunction "2_2") (pintype "passive"))
      (node (ref "U$5") (pin "P$2") (pinfunction "2_P$2") (pintype "bidirectional"))
    )
    (net (code "54") (name "FAULTL-ISO") (class "Default")
      (node (ref "C32") (pin "2") (pinfunction "2_2") (pintype "passive"))
      (node (ref "U$5") (pin "P$1") (pinfunction "1_P$1") (pintype "bidirectional"))
    )
    (net (code "55") (name "GATE16") (class "Default")
      (node (ref "R56") (pin "2") (pinfunction "2_2") (pintype "passive"))
      (node (ref "TR50") (pin "2") (pinfunction "2_2") (pintype "passive"))
      (node (ref "U$25") (pin "1") (pinfunction "G_1") (pintype "passive"))
    )
    (net (code "56") (name "GND") (class "Default")
      (node (ref "C") (pin "30") (pinfunction "DGND1_30") (pintype "bidirectional"))
      (node (ref "C") (pin "35") (pinfunction "DGND2_35") (pintype "bidirectional"))
      (node (ref "C") (pin "37") (pinfunction "DGND3_37") (pintype "bidirectional"))
      (node (ref "C") (pin "48") (pinfunction "CGND_48") (pintype "bidirectional"))
      (node (ref "C") (pin "69") (pinfunction "AGND3_69") (pintype "bidirectional"))
      (node (ref "C") (pin "72") (pinfunction "AGND2_72") (pintype "bidirectional"))
      (node (ref "C") (pin "74") (pinfunction "AGND1_74") (pintype "bidirectional"))
      (node (ref "C1") (pin "2") (pinfunction "2_2") (pintype "passive"))
      (node (ref "C10") (pin "2") (pinfunction "2_2") (pintype "passive"))
      (node (ref "C11") (pin "2") (pinfunction "2_2") (pintype "passive"))
      (node (ref "C12") (pin "2") (pinfunction "2_2") (pintype "passive"))
      (node (ref "C13") (pin "2") (pinfunction "2_2") (pintype "passive"))
      (node (ref "C14") (pin "2") (pinfunction "2_2") (pintype "passive"))
      (node (ref "C15") (pin "2") (pinfunction "2_2") (pintype "passive"))
      (node (ref "C16") (pin "2") (pinfunction "2_2") (pintype "passive"))
      (node (ref "C17") (pin "2") (pinfunction "2_2") (pintype "passive"))
      (node (ref "C18") (pin "2") (pinfunction "2_2") (pintype "passive"))
      (node (ref "C19") (pin "2") (pinfunction "2_2") (pintype "passive"))
      (node (ref "C2") (pin "2") (pinfunction "2_2") (pintype "passive"))
      (node (ref "C20") (pin "2") (pinfunction "2_2") (pintype "passive"))
      (node (ref "C21") (pin "2") (pinfunction "2_2") (pintype "passive"))
      (node (ref "C22") (pin "2") (pinfunction "2_2") (pintype "passive"))
      (node (ref "C25") (pin "2") (pinfunction "2_2") (pintype "passive"))
      (node (ref "C26") (pin "2") (pinfunction "2_2") (pintype "passive"))
      (node (ref "C27") (pin "2") (pinfunction "2_2") (pintype "passive"))
      (node (ref "C28") (pin "2") (pinfunction "2_2") (pintype "passive"))
      (node (ref "C29") (pin "2") (pinfunction "2_2") (pintype "passive"))
      (node (ref "C3") (pin "2") (pinfunction "2_2") (pintype "passive"))
      (node (ref "C4") (pin "2") (pinfunction "2_2") (pintype "passive"))
      (node (ref "C5") (pin "2") (pinfunction "2_2") (pintype "passive"))
      (node (ref "C6") (pin "2") (pinfunction "2_2") (pintype "passive"))
      (node (ref "C7") (pin "2") (pinfunction "2_2") (pintype "passive"))
      (node (ref "C8") (pin "2") (pinfunction "2_2") (pintype "passive"))
      (node (ref "C9") (pin "2") (pinfunction "2_2") (pintype "passive"))
      (node (ref "D10") (pin "A") (pinfunction "A_A") (pintype "passive"))
      (node (ref "D11") (pin "C") (pinfunction "C_C") (pintype "passive"))
      (node (ref "D12") (pin "3") (pinfunction "3_3") (pintype "passive"))
      (node (ref "D13") (pin "3") (pinfunction "3_3") (pintype "passive"))
      (node (ref "D14") (pin "3") (pinfunction "3_3") (pintype "passive"))
      (node (ref "D15") (pin "3") (pinfunction "3_3") (pintype "passive"))
      (node (ref "D16") (pin "3") (pinfunction "3_3") (pintype "passive"))
      (node (ref "D17") (pin "3") (pinfunction "3_3") (pintype "passive"))
      (node (ref "D18") (pin "3") (pinfunction "3_3") (pintype "passive"))
      (node (ref "D19") (pin "3") (pinfunction "3_3") (pintype "passive"))
      (node (ref "D5") (pin "A") (pinfunction "A_A") (pintype "passive"))
      (node (ref "D7") (pin "A") (pinfunction "A_A") (pintype "passive"))
      (node (ref "D8") (pin "C") (pinfunction "C_C") (pintype "passive"))
      (node (ref "D9") (pin "A") (pinfunction "A_A") (pintype "passive"))
      (node (ref "FAULTPMOS") (pin "3") (pinfunction "D_3") (pintype "passive"))
      (node (ref "FAULTPMOS1") (pin "3") (pinfunction "D_3") (pintype "passive"))
      (node (ref "R38") (pin "1") (pinfunction "1_1") (pintype "passive"))
      (node (ref "R82") (pin "1") (pinfunction "1_1") (pintype "passive"))
      (node (ref "R85") (pin "1") (pinfunction "1_1") (pintype "passive"))
      (node (ref "T") (pin "30") (pinfunction "DGND1_30") (pintype "bidirectional"))
      (node (ref "T") (pin "35") (pinfunction "DGND2_35") (pintype "bidirectional"))
      (node (ref "T") (pin "37") (pinfunction "DGND3_37") (pintype "bidirectional"))
      (node (ref "T") (pin "48") (pinfunction "CGND_48") (pintype "bidirectional"))
      (node (ref "T") (pin "69") (pinfunction "AGND3_69") (pintype "bidirectional"))
      (node (ref "T") (pin "72") (pinfunction "AGND2_72") (pintype "bidirectional"))
      (node (ref "T") (pin "74") (pinfunction "AGND1_74") (pintype "bidirectional"))
    )
    (net (code "57") (name "NPNB_C") (class "Default")
      (node (ref "C") (pin "71") (pinfunction "NPNB_71") (pintype "bidirectional"))
      (node (ref "U$4") (pin "B1") (pinfunction "B_B1") (pintype "passive"))
    )
    (net (code "58") (name "NPNB_T") (class "Default")
      (node (ref "T") (pin "71") (pinfunction "NPNB_71") (pintype "bidirectional"))
      (node (ref "U$4") (pin "B2") (pinfunction "B_B2") (pintype "passive"))
    )
    (net (code "59") (name "Net-(C20-Pad1)") (class "Default")
      (node (ref "C20") (pin "1") (pinfunction "1_1") (pintype "passive"))
      (node (ref "R5") (pin "1") (pinfunction "1_1") (pintype "passive"))
    )
    (net (code "60") (name "Net-(C21-Pad1)") (class "Default")
      (node (ref "C21") (pin "1") (pinfunction "1_1") (pintype "passive"))
      (node (ref "R6") (pin "1") (pinfunction "1_1") (pintype "passive"))
    )
    (net (code "61") (name "Net-(C38-Pad1)") (class "Default")
      (node (ref "C38") (pin "1") (pinfunction "1_1") (pintype "passive"))
      (node (ref "R71") (pin "2") (pinfunction "2_2") (pintype "passive"))
    )
    (net (code "62") (name "Net-(C38-Pad2)") (class "Default")
      (node (ref "C38") (pin "2") (pinfunction "2_2") (pintype "passive"))
      (node (ref "R70") (pin "2") (pinfunction "2_2") (pintype "passive"))
    )
    (net (code "63") (name "Net-(C39-Pad1)") (class "Default")
      (node (ref "C39") (pin "1") (pinfunction "1_1") (pintype "passive"))
      (node (ref "R72") (pin "2") (pinfunction "2_2") (pintype "passive"))
    )
    (net (code "64") (name "Net-(C39-Pad2)") (class "Default")
      (node (ref "C39") (pin "2") (pinfunction "2_2") (pintype "passive"))
      (node (ref "R69") (pin "2") (pinfunction "2_2") (pintype "passive"))
    )
    (net (code "65") (name "Net-(C40-Pad1)") (class "Default")
      (node (ref "C40") (pin "1") (pinfunction "1_1") (pintype "passive"))
      (node (ref "R73") (pin "2") (pinfunction "2_2") (pintype "passive"))
    )
    (net (code "66") (name "Net-(C40-Pad2)") (class "Default")
      (node (ref "C40") (pin "2") (pinfunction "2_2") (pintype "passive"))
      (node (ref "R68") (pin "2") (pinfunction "2_2") (pintype "passive"))
    )
    (net (code "67") (name "Net-(C41-Pad1)") (class "Default")
      (node (ref "C41") (pin "1") (pinfunction "1_1") (pintype "passive"))
      (node (ref "R74") (pin "2") (pinfunction "2_2") (pintype "passive"))
    )
    (net (code "68") (name "Net-(C41-Pad2)") (class "Default")
      (node (ref "C41") (pin "2") (pinfunction "2_2") (pintype "passive"))
      (node (ref "R67") (pin "2") (pinfunction "2_2") (pintype "passive"))
    )
    (net (code "69") (name "Net-(CB-FAULT_N)") (class "Default")
      (node (ref "C") (pin "40") (pinfunction "FAULT_N_40") (pintype "bidirectional"))
      (node (ref "FAULTPMOS1") (pin "1") (pinfunction "G_1") (pintype "passive"))
    )
    (net (code "70") (name "Net-(CB-RX)") (class "Default")
      (node (ref "C") (pin "39") (pinfunction "RX_39") (pintype "bidirectional"))
      (node (ref "JP2") (pin "2") (pinfunction "2_2") (pintype "passive"))
      (node (ref "R83") (pin "1") (pinfunction "1_1") (pintype "passive"))
    )
    (net (code "71") (name "Net-(CB-TX)") (class "Default")
      (node (ref "C") (pin "38") (pinfunction "TX_38") (pintype "bidirectional"))
      (node (ref "JP2") (pin "1") (pinfunction "1_1") (pintype "passive"))
      (node (ref "R84") (pin "1") (pinfunction "1_1") (pintype "passive"))
    )
    (net (code "72") (name "Net-(CB-WAKEUP)") (class "Default")
      (node (ref "C") (pin "49") (pinfunction "WAKEUP_49") (pintype "bidirectional"))
      (node (ref "JP2") (pin "3") (pinfunction "3_3") (pintype "passive"))
      (node (ref "R85") (pin "2") (pinfunction "2_2") (pintype "passive"))
    )
    (net (code "73") (name "Net-(CE-CHM)") (class "Default")
      (node (ref "C") (pin "33") (pinfunction "CHM_33") (pintype "bidirectional"))
      (node (ref "C23") (pin "2") (pinfunction "2_2") (pintype "passive"))
    )
    (net (code "74") (name "Net-(CE-CHP)") (class "Default")
      (node (ref "C") (pin "32") (pinfunction "CHP_32") (pintype "bidirectional"))
      (node (ref "C23") (pin "1") (pinfunction "1_1") (pintype "passive"))
    )
    (net (code "75") (name "Net-(CE-OUT1)") (class "Default")
      (node (ref "C") (pin "68") (pinfunction "OUT2_68") (pintype "bidirectional"))
      (node (ref "C") (pin "73") (pinfunction "OUT1_73") (pintype "bidirectional"))
      (node (ref "C1") (pin "1") (pinfunction "1_1") (pintype "passive"))
    )
    (net (code "76") (name "Net-(ENABLED_LED1-A)") (class "Default")
      (node (ref "ENABLED_LED1") (pin "1") (pinfunction "A_1") (pintype "passive"))
      (node (ref "R75") (pin "2") (pinfunction "2_2") (pintype "passive"))
    )
    (net (code "77") (name "Net-(ENABLED_LED1-C)") (class "Default")
      (node (ref "ENABLED_LED1") (pin "2") (pinfunction "C_2") (pintype "passive"))
      (node (ref "FAULTPMOS") (pin "2") (pinfunction "S_2") (pintype "passive"))
    )
    (net (code "78") (name "Net-(ENABLED_LED2-PadA)") (class "Default")
      (node (ref "ENABLED_LED2") (pin "A") (pinfunction "A_A") (pintype "passive"))
      (node (ref "R53") (pin "2") (pinfunction "2_2") (pintype "passive"))
    )
    (net (code "79") (name "Net-(ENABLED_LED3-A)") (class "Default")
      (node (ref "ENABLED_LED3") (pin "1") (pinfunction "A_1") (pintype "passive"))
      (node (ref "R76") (pin "2") (pinfunction "2_2") (pintype "passive"))
    )
    (net (code "80") (name "Net-(ENABLED_LED3-C)") (class "Default")
      (node (ref "ENABLED_LED3") (pin "2") (pinfunction "C_2") (pintype "passive"))
      (node (ref "FAULTPMOS1") (pin "2") (pinfunction "S_2") (pintype "passive"))
    )
    (net (code "81") (name "Net-(FAULTPMOS-G)") (class "Default")
      (node (ref "FAULTPMOS") (pin "1") (pinfunction "G_1") (pintype "passive"))
      (node (ref "T") (pin "40") (pinfunction "FAULT_N_40") (pintype "bidirectional"))
    )
    (net (code "82") (name "Net-(R3-Pad2)") (class "Default")
      (node (ref "R3") (pin "2") (pinfunction "2_2") (pintype "passive"))
      (node (ref "U$3") (pin "$P8") (pinfunction "$P8_$P8") (pintype "passive"))
    )
    (net (code "83") (name "Net-(R4-Pad2)") (class "Default")
      (node (ref "R4") (pin "2") (pinfunction "2_2") (pintype "passive"))
      (node (ref "U$3") (pin "$P5") (pinfunction "$P5_$P5") (pintype "passive"))
    )
    (net (code "84") (name "Net-(R10-Pad1)") (class "Default")
      (node (ref "R10") (pin "1") (pinfunction "1_1") (pintype "passive"))
      (node (ref "R26") (pin "2") (pinfunction "2_2") (pintype "passive"))
      (node (ref "R41") (pin "2") (pinfunction "2_2") (pintype "passive"))
      (node (ref "R51") (pin "1") (pinfunction "1_1") (pintype "passive"))
    )
    (net (code "85") (name "Net-(R11-Pad1)") (class "Default")
      (node (ref "R11") (pin "1") (pinfunction "1_1") (pintype "passive"))
      (node (ref "R27") (pin "2") (pinfunction "2_2") (pintype "passive"))
      (node (ref "R42") (pin "1") (pinfunction "1_1") (pintype "passive"))
      (node (ref "R51") (pin "2") (pinfunction "2_2") (pintype "passive"))
    )
    (net (code "86") (name "Net-(R12-Pad1)") (class "Default")
      (node (ref "R12") (pin "1") (pinfunction "1_1") (pintype "passive"))
      (node (ref "R28") (pin "2") (pinfunction "2_2") (pintype "passive"))
      (node (ref "R42") (pin "2") (pinfunction "2_2") (pintype "passive"))
      (node (ref "R52") (pin "1") (pinfunction "1_1") (pintype "passive"))
    )
    (net (code "87") (name "Net-(R13-Pad1)") (class "Default")
      (node (ref "R13") (pin "1") (pinfunction "1_1") (pintype "passive"))
      (node (ref "R29") (pin "2") (pinfunction "2_2") (pintype "passive"))
      (node (ref "R43") (pin "1") (pinfunction "1_1") (pintype "passive"))
      (node (ref "R52") (pin "2") (pinfunction "2_2") (pintype "passive"))
    )
    (net (code "88") (name "Net-(R14-Pad1)") (class "Default")
      (node (ref "R14") (pin "1") (pinfunction "1_1") (pintype "passive"))
      (node (ref "R30") (pin "2") (pinfunction "2_2") (pintype "passive"))
      (node (ref "R43") (pin "2") (pinfunction "2_2") (pintype "passive"))
      (node (ref "R54") (pin "1") (pinfunction "1_1") (pintype "passive"))
    )
    (net (code "89") (name "Net-(R15-Pad1)") (class "Default")
      (node (ref "R15") (pin "1") (pinfunction "1_1") (pintype "passive"))
      (node (ref "R31") (pin "2") (pinfunction "2_2") (pintype "passive"))
      (node (ref "R44") (pin "1") (pinfunction "1_1") (pintype "passive"))
      (node (ref "R54") (pin "2") (pinfunction "2_2") (pintype "passive"))
    )
    (net (code "90") (name "Net-(R16-Pad1)") (class "Default")
      (node (ref "R16") (pin "1") (pinfunction "1_1") (pintype "passive"))
      (node (ref "R32") (pin "2") (pinfunction "2_2") (pintype "passive"))
      (node (ref "R44") (pin "2") (pinfunction "2_2") (pintype "passive"))
      (node (ref "R55") (pin "1") (pinfunction "1_1") (pintype "passive"))
    )
    (net (code "91") (name "Net-(R17-Pad1)") (class "Default")
      (node (ref "R17") (pin "1") (pinfunction "1_1") (pintype "passive"))
      (node (ref "R33") (pin "2") (pinfunction "2_2") (pintype "passive"))
      (node (ref "R45") (pin "1") (pinfunction "1_1") (pintype "passive"))
      (node (ref "R55") (pin "2") (pinfunction "2_2") (pintype "passive"))
    )
    (net (code "92") (name "Net-(R18-Pad1)") (class "Default")
      (node (ref "R18") (pin "1") (pinfunction "1_1") (pintype "passive"))
      (node (ref "R34") (pin "2") (pinfunction "2_2") (pintype "passive"))
      (node (ref "R45") (pin "2") (pinfunction "2_2") (pintype "passive"))
      (node (ref "R57") (pin "1") (pinfunction "1_1") (pintype "passive"))
    )
    (net (code "93") (name "Net-(R19-Pad1)") (class "Default")
      (node (ref "R19") (pin "1") (pinfunction "1_1") (pintype "passive"))
      (node (ref "R35") (pin "2") (pinfunction "2_2") (pintype "passive"))
      (node (ref "R46") (pin "1") (pinfunction "1_1") (pintype "passive"))
      (node (ref "R57") (pin "2") (pinfunction "2_2") (pintype "passive"))
    )
    (net (code "94") (name "Net-(R20-Pad1)") (class "Default")
      (node (ref "R20") (pin "1") (pinfunction "1_1") (pintype "passive"))
      (node (ref "R36") (pin "2") (pinfunction "2_2") (pintype "passive"))
      (node (ref "R46") (pin "2") (pinfunction "2_2") (pintype "passive"))
      (node (ref "R58") (pin "1") (pinfunction "1_1") (pintype "passive"))
    )
    (net (code "95") (name "Net-(R23-Pad2)") (class "Default")
      (node (ref "R23") (pin "2") (pinfunction "2_2") (pintype "passive"))
      (node (ref "R38") (pin "2") (pinfunction "2_2") (pintype "passive"))
      (node (ref "R40") (pin "1") (pinfunction "1_1") (pintype "passive"))
      (node (ref "R7") (pin "1") (pinfunction "1_1") (pintype "passive"))
    )
    (net (code "96") (name "Net-(R24-Pad2)") (class "Default")
      (node (ref "R24") (pin "2") (pinfunction "2_2") (pintype "passive"))
      (node (ref "R40") (pin "2") (pinfunction "2_2") (pintype "passive"))
      (node (ref "R50") (pin "1") (pinfunction "1_1") (pintype "passive"))
      (node (ref "R8") (pin "1") (pinfunction "1_1") (pintype "passive"))
    )
    (net (code "97") (name "Net-(R25-Pad2)") (class "Default")
      (node (ref "R25") (pin "2") (pinfunction "2_2") (pintype "passive"))
      (node (ref "R41") (pin "1") (pinfunction "1_1") (pintype "passive"))
      (node (ref "R50") (pin "2") (pinfunction "2_2") (pintype "passive"))
      (node (ref "R9") (pin "1") (pinfunction "1_1") (pintype "passive"))
    )
    (net (code "98") (name "Net-(TB-RX)") (class "Default")
      (node (ref "JP1") (pin "2") (pinfunction "2_2") (pintype "passive"))
      (node (ref "R80") (pin "1") (pinfunction "1_1") (pintype "passive"))
      (node (ref "T") (pin "39") (pinfunction "RX_39") (pintype "bidirectional"))
    )
    (net (code "99") (name "Net-(TB-TX)") (class "Default")
      (node (ref "JP1") (pin "1") (pinfunction "1_1") (pintype "passive"))
      (node (ref "R81") (pin "1") (pinfunction "1_1") (pintype "passive"))
      (node (ref "T") (pin "38") (pinfunction "TX_38") (pintype "bidirectional"))
    )
    (net (code "100") (name "Net-(TB-WAKEUP)") (class "Default")
      (node (ref "JP1") (pin "3") (pinfunction "3_3") (pintype "passive"))
      (node (ref "R82") (pin "2") (pinfunction "2_2") (pintype "passive"))
      (node (ref "T") (pin "49") (pinfunction "WAKEUP_49") (pintype "bidirectional"))
    )
    (net (code "101") (name "Net-(TE-CHM)") (class "Default")
      (node (ref "C24") (pin "2") (pinfunction "2_2") (pintype "passive"))
      (node (ref "T") (pin "33") (pinfunction "CHM_33") (pintype "bidirectional"))
    )
    (net (code "102") (name "Net-(TE-CHP)") (class "Default")
      (node (ref "C24") (pin "1") (pinfunction "1_1") (pintype "passive"))
      (node (ref "T") (pin "32") (pinfunction "CHP_32") (pintype "bidirectional"))
    )
    (net (code "103") (name "Net-(TE-OUT1)") (class "Default")
      (node (ref "C2") (pin "1") (pinfunction "1_1") (pintype "passive"))
      (node (ref "T") (pin "68") (pinfunction "OUT2_68") (pintype "bidirectional"))
      (node (ref "T") (pin "73") (pinfunction "OUT1_73") (pintype "bidirectional"))
    )
    (net (code "104") (name "Net-(U$2-2)") (class "Default")
      (node (ref "C31") (pin "1") (pinfunction "1_1") (pintype "passive"))
      (node (ref "U$2") (pin "P$2") (pinfunction "2_P$2") (pintype "bidirectional"))
    )
    (net (code "105") (name "Net-(U$2-3)") (class "Default")
      (node (ref "C30") (pin "1") (pinfunction "1_1") (pintype "passive"))
      (node (ref "U$2") (pin "P$3") (pinfunction "3_P$3") (pintype "bidirectional"))
    )
    (net (code "106") (name "Net-(U$6-2)") (class "Default")
      (node (ref "C33") (pin "1") (pinfunction "1_1") (pintype "passive"))
      (node (ref "U$6") (pin "P$2") (pinfunction "2_P$2") (pintype "bidirectional"))
    )
    (net (code "107") (name "Net-(U$6-3)") (class "Default")
      (node (ref "C32") (pin "1") (pinfunction "1_1") (pintype "passive"))
      (node (ref "U$6") (pin "P$3") (pinfunction "3_P$3") (pintype "bidirectional"))
    )
    (net (code "108") (name "Net-(U$8-2)") (class "Default")
      (node (ref "C36") (pin "1") (pinfunction "1_1") (pintype "passive"))
      (node (ref "U$8") (pin "P$2") (pinfunction "2_P$2") (pintype "bidirectional"))
    )
    (net (code "109") (name "Net-(U$8-3)") (class "Default")
      (node (ref "C37") (pin "1") (pinfunction "1_1") (pintype "passive"))
      (node (ref "U$8") (pin "P$3") (pinfunction "3_P$3") (pintype "bidirectional"))
    )
    (net (code "110") (name "Net-(U$9-2)") (class "Default")
      (node (ref "C34") (pin "1") (pinfunction "1_1") (pintype "passive"))
      (node (ref "U$9") (pin "P$2") (pinfunction "2_P$2") (pintype "bidirectional"))
    )
    (net (code "111") (name "Net-(U$9-3)") (class "Default")
      (node (ref "C35") (pin "1") (pinfunction "1_1") (pintype "passive"))
      (node (ref "U$9") (pin "P$3") (pinfunction "3_P$3") (pintype "bidirectional"))
    )
    (net (code "112") (name "Net-(U$10-1)") (class "Default")
      (node (ref "R59") (pin "2") (pinfunction "2_2") (pintype "passive"))
      (node (ref "U$10") (pin "P$1") (pinfunction "1_P$1") (pintype "bidirectional"))
    )
    (net (code "113") (name "Net-(U$10-2)") (class "Default")
      (node (ref "R60") (pin "2") (pinfunction "2_2") (pintype "passive"))
      (node (ref "U$10") (pin "P$2") (pinfunction "2_P$2") (pintype "bidirectional"))
    )
    (net (code "114") (name "Net-(U$10-3)") (class "Default")
      (node (ref "U$10") (pin "P$3") (pinfunction "3_P$3") (pintype "bidirectional"))
      (node (ref "U$2") (pin "P$1") (pinfunction "1_P$1") (pintype "bidirectional"))
    )
    (net (code "115") (name "Net-(U$10-4)") (class "Default")
      (node (ref "U$10") (pin "P$4") (pinfunction "4_P$4") (pintype "bidirectional"))
      (node (ref "U$2") (pin "P$4") (pinfunction "4_P$4") (pintype "bidirectional"))
    )
    (net (code "116") (name "Net-(U$12-1)") (class "Default")
      (node (ref "R61") (pin "2") (pinfunction "2_2") (pintype "passive"))
      (node (ref "U$12") (pin "P$1") (pinfunction "1_P$1") (pintype "bidirectional"))
    )
    (net (code "117") (name "Net-(U$12-2)") (class "Default")
      (node (ref "R62") (pin "2") (pinfunction "2_2") (pintype "passive"))
      (node (ref "U$12") (pin "P$2") (pinfunction "2_P$2") (pintype "bidirectional"))
    )
    (net (code "118") (name "Net-(U$12-3)") (class "Default")
      (node (ref "U$12") (pin "P$3") (pinfunction "3_P$3") (pintype "bidirectional"))
      (node (ref "U$6") (pin "P$1") (pinfunction "1_P$1") (pintype "bidirectional"))
    )
    (net (code "119") (name "Net-(U$12-4)") (class "Default")
      (node (ref "U$12") (pin "P$4") (pinfunction "4_P$4") (pintype "bidirectional"))
      (node (ref "U$6") (pin "P$4") (pinfunction "4_P$4") (pintype "bidirectional"))
    )
    (net (code "120") (name "Net-(U$14-1)") (class "Default")
      (node (ref "U$14") (pin "P$1") (pinfunction "1_P$1") (pintype "bidirectional"))
      (node (ref "U$9") (pin "P$1") (pinfunction "1_P$1") (pintype "bidirectional"))
    )
    (net (code "121") (name "Net-(U$14-2)") (class "Default")
      (node (ref "U$14") (pin "P$2") (pinfunction "2_P$2") (pintype "bidirectional"))
      (node (ref "U$9") (pin "P$4") (pinfunction "4_P$4") (pintype "bidirectional"))
    )
    (net (code "122") (name "Net-(U$14-3)") (class "Default")
      (node (ref "R64") (pin "1") (pinfunction "1_1") (pintype "passive"))
      (node (ref "U$14") (pin "P$3") (pinfunction "3_P$3") (pintype "bidirectional"))
    )
    (net (code "123") (name "Net-(U$14-4)") (class "Default")
      (node (ref "R63") (pin "1") (pinfunction "1_1") (pintype "passive"))
      (node (ref "U$14") (pin "P$4") (pinfunction "4_P$4") (pintype "bidirectional"))
    )
    (net (code "124") (name "Net-(U$16-1)") (class "Default")
      (node (ref "U$16") (pin "P$1") (pinfunction "1_P$1") (pintype "bidirectional"))
      (node (ref "U$8") (pin "P$1") (pinfunction "1_P$1") (pintype "bidirectional"))
    )
    (net (code "125") (name "Net-(U$16-2)") (class "Default")
      (node (ref "U$16") (pin "P$2") (pinfunction "2_P$2") (pintype "bidirectional"))
      (node (ref "U$8") (pin "P$4") (pinfunction "4_P$4") (pintype "bidirectional"))
    )
    (net (code "126") (name "Net-(U$16-3)") (class "Default")
      (node (ref "R66") (pin "1") (pinfunction "1_1") (pintype "passive"))
      (node (ref "U$16") (pin "P$3") (pinfunction "3_P$3") (pintype "bidirectional"))
    )
    (net (code "127") (name "Net-(U$16-4)") (class "Default")
      (node (ref "R65") (pin "1") (pinfunction "1_1") (pintype "passive"))
      (node (ref "U$16") (pin "P$4") (pinfunction "4_P$4") (pintype "bidirectional"))
    )
    (net (code "128") (name "Net-(U$25-D)") (class "Default")
      (node (ref "ENABLED_LED2") (pin "C") (pinfunction "C_C") (pintype "passive"))
      (node (ref "U$23") (pin "2") (pinfunction "2_2") (pintype "passive"))
      (node (ref "U$25") (pin "2") (pinfunction "D_2") (pintype "passive"))
    )
    (net (code "129") (name "ON+") (class "Default")
      (node (ref "U$3") (pin "$P12") (pinfunction "$P12_$P12") (pintype "bidirectional"))
      (node (ref "U$7") (pin "P$6") (pinfunction "6_P$6") (pintype "bidirectional"))
    )
    (net (code "130") (name "ON-") (class "Default")
      (node (ref "U$3") (pin "$P1") (pinfunction "$P1_$P1") (pintype "bidirectional"))
      (node (ref "U$7") (pin "P$5") (pinfunction "5_P$5") (pintype "bidirectional"))
    )
    (net (code "131") (name "TEMP16") (class "Default")
      (node (ref "R22") (pin "1") (pinfunction "1_1") (pintype "passive"))
      (node (ref "R47") (pin "1") (pinfunction "1_1") (pintype "passive"))
      (node (ref "U$1") (pin "2") (pinfunction "TEMP+_2") (pintype "bidirectional"))
    )
    (net (code "132") (name "TOP") (class "Default")
      (node (ref "U$4") (pin "C1") (pinfunction "C_C1") (pintype "passive"))
      (node (ref "U$4") (pin "C2") (pinfunction "C_C2") (pintype "passive"))
    )
    (net (code "133") (name "T_CELL_EQ1") (class "Default")
      (node (ref "T") (pin "28") (pinfunction "EQ1_28") (pintype "bidirectional"))
    )
    (net (code "134") (name "T_CELL_EQ2") (class "Default")
      (node (ref "T") (pin "26") (pinfunction "EQ2_26") (pintype "bidirectional"))
    )
    (net (code "135") (name "T_CELL_EQ3") (class "Default")
      (node (ref "T") (pin "24") (pinfunction "EQ3_24") (pintype "bidirectional"))
    )
    (net (code "136") (name "T_CELL_EQ4") (class "Default")
      (node (ref "T") (pin "22") (pinfunction "EQ4_22") (pintype "bidirectional"))
    )
    (net (code "137") (name "T_CELL_EQ5") (class "Default")
      (node (ref "T") (pin "20") (pinfunction "EQ5_20") (pintype "bidirectional"))
    )
    (net (code "138") (name "T_CELL_EQ6") (class "Default")
      (node (ref "T") (pin "18") (pinfunction "EQ6_18") (pintype "bidirectional"))
    )
    (net (code "139") (name "T_CELL_EQ7") (class "Default")
      (node (ref "T") (pin "16") (pinfunction "EQ7_16") (pintype "bidirectional"))
    )
    (net (code "140") (name "T_CELL_EQ8") (class "Default")
      (node (ref "T") (pin "14") (pinfunction "EQ8_14") (pintype "bidirectional"))
    )
    (net (code "141") (name "T_CELL_EQ9") (class "Default")
      (node (ref "T") (pin "12") (pinfunction "EQ9_12") (pintype "bidirectional"))
    )
    (net (code "142") (name "T_CELL_EQ10") (class "Default")
      (node (ref "T") (pin "10") (pinfunction "EQ10_10") (pintype "bidirectional"))
    )
    (net (code "143") (name "T_CELL_EQ11") (class "Default")
      (node (ref "T") (pin "8") (pinfunction "EQ11_8") (pintype "bidirectional"))
    )
    (net (code "144") (name "T_CELL_EQ12") (class "Default")
      (node (ref "T") (pin "6") (pinfunction "EQ12_6") (pintype "bidirectional"))
    )
    (net (code "145") (name "T_CELL_EQ13") (class "Default")
      (node (ref "T") (pin "4") (pinfunction "EQ13_4") (pintype "bidirectional"))
    )
    (net (code "146") (name "T_CELL_EQ14") (class "Default")
      (node (ref "T") (pin "2") (pinfunction "EQ14_2") (pintype "bidirectional"))
    )
    (net (code "147") (name "T_CELL_EQ15") (class "Default")
      (node (ref "T") (pin "80") (pinfunction "EQ15_80") (pintype "bidirectional"))
    )
    (net (code "148") (name "T_CELL_EQ16") (class "Default")
      (node (ref "T") (pin "78") (pinfunction "EQ16_78") (pintype "bidirectional"))
    )
    (net (code "149") (name "T_CELL_TOP") (class "Default")
      (node (ref "C28") (pin "1") (pinfunction "1_1") (pintype "passive"))
      (node (ref "D4") (pin "C") (pinfunction "C_C") (pintype "passive"))
      (node (ref "D6") (pin "A") (pinfunction "A_A") (pintype "passive"))
      (node (ref "R48") (pin "2") (pinfunction "2_2") (pintype "passive"))
      (node (ref "T") (pin "76") (pinfunction "TOP_76") (pintype "bidirectional"))
    )
    (net (code "150") (name "T_CELL_VSENSE0") (class "Default")
      (node (ref "C29") (pin "1") (pinfunction "1_1") (pintype "passive"))
      (node (ref "D7") (pin "C") (pinfunction "C_C") (pintype "passive"))
      (node (ref "D8") (pin "A") (pinfunction "A_A") (pintype "passive"))
      (node (ref "T") (pin "29") (pinfunction "VSENSE0_29") (pintype "bidirectional"))
    )
    (net (code "151") (name "T_CELL_VSENSE1") (class "Default")
      (node (ref "R7") (pin "2") (pinfunction "2_2") (pintype "passive"))
      (node (ref "T") (pin "27") (pinfunction "VSENSE1_27") (pintype "bidirectional"))
    )
    (net (code "152") (name "T_CELL_VSENSE2") (class "Default")
      (node (ref "R8") (pin "2") (pinfunction "2_2") (pintype "passive"))
      (node (ref "T") (pin "25") (pinfunction "VSENSE2_25") (pintype "bidirectional"))
    )
    (net (code "153") (name "T_CELL_VSENSE3") (class "Default")
      (node (ref "R9") (pin "2") (pinfunction "2_2") (pintype "passive"))
      (node (ref "T") (pin "23") (pinfunction "VSENSE3_23") (pintype "bidirectional"))
    )
    (net (code "154") (name "T_CELL_VSENSE4") (class "Default")
      (node (ref "R10") (pin "2") (pinfunction "2_2") (pintype "passive"))
      (node (ref "T") (pin "21") (pinfunction "VSENSE4_21") (pintype "bidirectional"))
    )
    (net (code "155") (name "T_CELL_VSENSE5") (class "Default")
      (node (ref "R11") (pin "2") (pinfunction "2_2") (pintype "passive"))
      (node (ref "T") (pin "19") (pinfunction "VSENSE5_19") (pintype "bidirectional"))
    )
    (net (code "156") (name "T_CELL_VSENSE6") (class "Default")
      (node (ref "R12") (pin "2") (pinfunction "2_2") (pintype "passive"))
      (node (ref "T") (pin "17") (pinfunction "VSENSE6_17") (pintype "bidirectional"))
    )
    (net (code "157") (name "T_CELL_VSENSE7") (class "Default")
      (node (ref "R13") (pin "2") (pinfunction "2_2") (pintype "passive"))
      (node (ref "T") (pin "15") (pinfunction "VSENSE7_15") (pintype "bidirectional"))
    )
    (net (code "158") (name "T_CELL_VSENSE8") (class "Default")
      (node (ref "R14") (pin "2") (pinfunction "2_2") (pintype "passive"))
      (node (ref "T") (pin "13") (pinfunction "VSENSE8_13") (pintype "bidirectional"))
    )
    (net (code "159") (name "T_CELL_VSENSE9") (class "Default")
      (node (ref "R15") (pin "2") (pinfunction "2_2") (pintype "passive"))
      (node (ref "T") (pin "11") (pinfunction "VSENSE9_11") (pintype "bidirectional"))
    )
    (net (code "160") (name "T_CELL_VSENSE10") (class "Default")
      (node (ref "R16") (pin "2") (pinfunction "2_2") (pintype "passive"))
      (node (ref "T") (pin "9") (pinfunction "VSENSE10_9") (pintype "bidirectional"))
    )
    (net (code "161") (name "T_CELL_VSENSE11") (class "Default")
      (node (ref "R17") (pin "2") (pinfunction "2_2") (pintype "passive"))
      (node (ref "T") (pin "7") (pinfunction "VSENSE11_7") (pintype "bidirectional"))
    )
    (net (code "162") (name "T_CELL_VSENSE12") (class "Default")
      (node (ref "R18") (pin "2") (pinfunction "2_2") (pintype "passive"))
      (node (ref "T") (pin "5") (pinfunction "VSENSE12_5") (pintype "bidirectional"))
    )
    (net (code "163") (name "T_CELL_VSENSE13") (class "Default")
      (node (ref "R19") (pin "2") (pinfunction "2_2") (pintype "passive"))
      (node (ref "T") (pin "3") (pinfunction "VSENSE13_3") (pintype "bidirectional"))
    )
    (net (code "164") (name "T_CELL_VSENSE14") (class "Default")
      (node (ref "R20") (pin "2") (pinfunction "2_2") (pintype "passive"))
      (node (ref "T") (pin "1") (pinfunction "VSENSE14_1") (pintype "bidirectional"))
    )
    (net (code "165") (name "T_CELL_VSENSE15") (class "Default")
      (node (ref "R21") (pin "2") (pinfunction "2_2") (pintype "passive"))
      (node (ref "T") (pin "79") (pinfunction "VSENSE15_79") (pintype "bidirectional"))
    )
    (net (code "166") (name "T_CELL_VSENSE16") (class "Default")
      (node (ref "D4") (pin "A") (pinfunction "A_A") (pintype "passive"))
      (node (ref "D6") (pin "C") (pinfunction "C_C") (pintype "passive"))
      (node (ref "R22") (pin "2") (pinfunction "2_2") (pintype "passive"))
      (node (ref "T") (pin "77") (pinfunction "VSENSE16_77") (pintype "bidirectional"))
    )
    (net (code "167") (name "T_COMMH+") (class "Default")
      (node (ref "D15") (pin "1") (pinfunction "1_1") (pintype "passive"))
      (node (ref "R64") (pin "2") (pinfunction "2_2") (pintype "passive"))
      (node (ref "T") (pin "55") (pinfunction "COMMH+_55") (pintype "bidirectional"))
    )
    (net (code "168") (name "T_COMMH-") (class "Default")
      (node (ref "D15") (pin "2") (pinfunction "2_2") (pintype "passive"))
      (node (ref "R63") (pin "2") (pinfunction "2_2") (pintype "passive"))
      (node (ref "T") (pin "54") (pinfunction "COMMH-_54") (pintype "bidirectional"))
    )
    (net (code "169") (name "T_COMML+") (class "Default")
      (node (ref "D18") (pin "2") (pinfunction "2_2") (pintype "passive"))
      (node (ref "R72") (pin "1") (pinfunction "1_1") (pintype "passive"))
      (node (ref "T") (pin "52") (pinfunction "COMML+_52") (pintype "bidirectional"))
    )
    (net (code "170") (name "T_COMML-") (class "Default")
      (node (ref "D18") (pin "1") (pinfunction "1_1") (pintype "passive"))
      (node (ref "R71") (pin "1") (pinfunction "1_1") (pintype "passive"))
      (node (ref "T") (pin "53") (pinfunction "COMML-_53") (pintype "bidirectional"))
    )
    (net (code "171") (name "T_FAULTH+") (class "Default")
      (node (ref "D17") (pin "1") (pinfunction "1_1") (pintype "passive"))
      (node (ref "R66") (pin "2") (pinfunction "2_2") (pintype "passive"))
      (node (ref "T") (pin "57") (pinfunction "FAULTH+_57") (pintype "bidirectional"))
    )
    (net (code "172") (name "T_FAULTH-") (class "Default")
      (node (ref "D17") (pin "2") (pinfunction "2_2") (pintype "passive"))
      (node (ref "R65") (pin "2") (pinfunction "2_2") (pintype "passive"))
      (node (ref "T") (pin "56") (pinfunction "FAULTH-_56") (pintype "bidirectional"))
    )
    (net (code "173") (name "T_FAULTL+") (class "Default")
      (node (ref "D19") (pin "2") (pinfunction "2_2") (pintype "passive"))
      (node (ref "R74") (pin "1") (pinfunction "1_1") (pintype "passive"))
      (node (ref "T") (pin "50") (pinfunction "FAULTL+_50") (pintype "bidirectional"))
    )
    (net (code "174") (name "T_FAULTL-") (class "Default")
      (node (ref "D19") (pin "1") (pinfunction "1_1") (pintype "passive"))
      (node (ref "R73") (pin "1") (pinfunction "1_1") (pintype "passive"))
      (node (ref "T") (pin "51") (pinfunction "FAULTL-_51") (pintype "bidirectional"))
    )
    (net (code "175") (name "V5VAO_C") (class "Default")
      (node (ref "C") (pin "58") (pinfunction "V5VAO_58") (pintype "bidirectional"))
      (node (ref "C3") (pin "1") (pinfunction "1_1") (pintype "passive"))
    )
    (net (code "176") (name "V5VAO_T") (class "Default")
      (node (ref "C4") (pin "1") (pinfunction "1_1") (pintype "passive"))
      (node (ref "T") (pin "58") (pinfunction "V5VAO_58") (pintype "bidirectional"))
    )
    (net (code "177") (name "VDIG_C") (class "Default")
      (node (ref "C") (pin "34") (pinfunction "VDIG_34") (pintype "bidirectional"))
      (node (ref "C15") (pin "1") (pinfunction "1_1") (pintype "passive"))
      (node (ref "C16") (pin "1") (pinfunction "1_1") (pintype "passive"))
      (node (ref "R1") (pin "1") (pinfunction "1_1") (pintype "passive"))
    )
    (net (code "178") (name "VDIG_T") (class "Default")
      (node (ref "C17") (pin "1") (pinfunction "1_1") (pintype "passive"))
      (node (ref "C18") (pin "1") (pinfunction "1_1") (pintype "passive"))
      (node (ref "R2") (pin "1") (pinfunction "1_1") (pintype "passive"))
      (node (ref "T") (pin "34") (pinfunction "VDIG_34") (pintype "bidirectional"))
    )
    (net (code "179") (name "VIO_C") (class "Default")
      (node (ref "C") (pin "41") (pinfunction "VIO_41") (pintype "bidirectional"))
      (node (ref "C13") (pin "1") (pinfunction "1_1") (pintype "passive"))
      (node (ref "R3") (pin "1") (pinfunction "1_1") (pintype "passive"))
    )
    (net (code "180") (name "VIO_T") (class "Default")
      (node (ref "C14") (pin "1") (pinfunction "1_1") (pintype "passive"))
      (node (ref "R4") (pin "1") (pinfunction "1_1") (pintype "passive"))
      (node (ref "T") (pin "41") (pinfunction "VIO_41") (pintype "bidirectional"))
    )
    (net (code "181") (name "VM_C") (class "Default")
      (node (ref "C") (pin "31") (pinfunction "VM_31") (pintype "bidirectional"))
      (node (ref "C10") (pin "1") (pinfunction "1_1") (pintype "passive"))
      (node (ref "C9") (pin "1") (pinfunction "1_1") (pintype "passive"))
    )
    (net (code "182") (name "VM_T") (class "Default")
      (node (ref "C11") (pin "1") (pinfunction "1_1") (pintype "passive"))
      (node (ref "C12") (pin "1") (pinfunction "1_1") (pintype "passive"))
      (node (ref "T") (pin "31") (pinfunction "VM_31") (pintype "bidirectional"))
    )
    (net (code "183") (name "VP_C") (class "Default")
      (node (ref "C") (pin "70") (pinfunction "VP_70") (pintype "bidirectional"))
      (node (ref "C19") (pin "1") (pinfunction "1_1") (pintype "passive"))
      (node (ref "R1") (pin "2") (pinfunction "2_2") (pintype "passive"))
      (node (ref "R5") (pin "2") (pinfunction "2_2") (pintype "passive"))
      (node (ref "U$3") (pin "$P9") (pinfunction "$P9_$P9") (pintype "passive"))
      (node (ref "U$4") (pin "E1") (pinfunction "E_E1") (pintype "passive"))
    )
    (net (code "184") (name "VP_T") (class "Default")
      (node (ref "C22") (pin "1") (pinfunction "1_1") (pintype "passive"))
      (node (ref "R2") (pin "2") (pinfunction "2_2") (pintype "passive"))
      (node (ref "R6") (pin "2") (pinfunction "2_2") (pintype "passive"))
      (node (ref "T") (pin "70") (pinfunction "VP_70") (pintype "bidirectional"))
      (node (ref "U$3") (pin "$P4") (pinfunction "$P4_$P4") (pintype "passive"))
      (node (ref "U$4") (pin "E2") (pinfunction "E_E2") (pintype "passive"))
    )
    (net (code "185") (name "VREF_C") (class "Default")
      (node (ref "C") (pin "67") (pinfunction "VREF_67") (pintype "bidirectional"))
      (node (ref "C5") (pin "1") (pinfunction "1_1") (pintype "passive"))
      (node (ref "C6") (pin "1") (pinfunction "1_1") (pintype "passive"))
    )
    (net (code "186") (name "VREF_T") (class "Default")
      (node (ref "C7") (pin "1") (pinfunction "1_1") (pintype "passive"))
      (node (ref "C8") (pin "1") (pinfunction "1_1") (pintype "passive"))
      (node (ref "T") (pin "67") (pinfunction "VREF_67") (pintype "bidirectional"))
    )
    (net (code "187") (name "unconnected-(CD-AUX0-Pad66)") (class "Default")
      (node (ref "C") (pin "66") (pinfunction "AUX0_66") (pintype "bidirectional"))
    )
    (net (code "188") (name "unconnected-(CD-AUX1-Pad65)") (class "Default")
      (node (ref "C") (pin "65") (pinfunction "AUX1_65") (pintype "bidirectional"))
    )
    (net (code "189") (name "unconnected-(CD-AUX2-Pad64)") (class "Default")
      (node (ref "C") (pin "64") (pinfunction "AUX2_64") (pintype "bidirectional"))
    )
    (net (code "190") (name "unconnected-(CD-AUX3-Pad63)") (class "Default")
      (node (ref "C") (pin "63") (pinfunction "AUX3_63") (pintype "bidirectional"))
    )
    (net (code "191") (name "unconnected-(CD-AUX4-Pad62)") (class "Default")
      (node (ref "C") (pin "62") (pinfunction "AUX4_62") (pintype "bidirectional"))
    )
    (net (code "192") (name "unconnected-(CD-AUX5-Pad61)") (class "Default")
      (node (ref "C") (pin "61") (pinfunction "AUX5_61") (pintype "bidirectional"))
    )
    (net (code "193") (name "unconnected-(CD-AUX6-Pad60)") (class "Default")
      (node (ref "C") (pin "60") (pinfunction "AUX6_60") (pintype "bidirectional"))
    )
    (net (code "194") (name "unconnected-(CD-AUX7-Pad59)") (class "Default")
      (node (ref "C") (pin "59") (pinfunction "AUX7_59") (pintype "bidirectional"))
    )
    (net (code "195") (name "unconnected-(CD-GPIO0-Pad47)") (class "Default")
      (node (ref "C") (pin "47") (pinfunction "GPIO0_47") (pintype "bidirectional"))
    )
    (net (code "196") (name "unconnected-(CD-GPIO1-Pad46)") (class "Default")
      (node (ref "C") (pin "46") (pinfunction "GPIO1_46") (pintype "bidirectional"))
    )
    (net (code "197") (name "unconnected-(CD-GPIO2-Pad45)") (class "Default")
      (node (ref "C") (pin "45") (pinfunction "GPIO2_45") (pintype "bidirectional"))
    )
    (net (code "198") (name "unconnected-(CD-GPIO3-Pad44)") (class "Default")
      (node (ref "C") (pin "44") (pinfunction "GPIO3_44") (pintype "bidirectional"))
    )
    (net (code "199") (name "unconnected-(CD-GPIO4-Pad43)") (class "Default")
      (node (ref "C") (pin "43") (pinfunction "GPIO4_43") (pintype "bidirectional"))
    )
    (net (code "200") (name "unconnected-(CD-GPIO5-Pad42)") (class "Default")
      (node (ref "C") (pin "42") (pinfunction "GPIO5_42") (pintype "bidirectional"))
    )
    (net (code "201") (name "unconnected-(CE-NC1-Pad36)") (class "Default")
      (node (ref "C") (pin "36") (pinfunction "NC1_36") (pintype "bidirectional"))
    )
    (net (code "202") (name "unconnected-(CE-NC2-Pad75)") (class "Default")
      (node (ref "C") (pin "75") (pinfunction "NC2_75") (pintype "bidirectional"))
    )
    (net (code "203") (name "unconnected-(TD-AUX0-Pad66)") (class "Default")
      (node (ref "T") (pin "66") (pinfunction "AUX0_66") (pintype "bidirectional"))
    )
    (net (code "204") (name "unconnected-(TD-AUX1-Pad65)") (class "Default")
      (node (ref "T") (pin "65") (pinfunction "AUX1_65") (pintype "bidirectional"))
    )
    (net (code "205") (name "unconnected-(TD-AUX2-Pad64)") (class "Default")
      (node (ref "T") (pin "64") (pinfunction "AUX2_64") (pintype "bidirectional"))
    )
    (net (code "206") (name "unconnected-(TD-AUX3-Pad63)") (class "Default")
      (node (ref "T") (pin "63") (pinfunction "AUX3_63") (pintype "bidirectional"))
    )
    (net (code "207") (name "unconnected-(TD-AUX4-Pad62)") (class "Default")
      (node (ref "T") (pin "62") (pinfunction "AUX4_62") (pintype "bidirectional"))
    )
    (net (code "208") (name "unconnected-(TD-AUX5-Pad61)") (class "Default")
      (node (ref "T") (pin "61") (pinfunction "AUX5_61") (pintype "bidirectional"))
    )
    (net (code "209") (name "unconnected-(TD-AUX6-Pad60)") (class "Default")
      (node (ref "T") (pin "60") (pinfunction "AUX6_60") (pintype "bidirectional"))
    )
    (net (code "210") (name "unconnected-(TD-AUX7-Pad59)") (class "Default")
      (node (ref "T") (pin "59") (pinfunction "AUX7_59") (pintype "bidirectional"))
    )
    (net (code "211") (name "unconnected-(TD-GPIO0-Pad47)") (class "Default")
      (node (ref "T") (pin "47") (pinfunction "GPIO0_47") (pintype "bidirectional"))
    )
    (net (code "212") (name "unconnected-(TD-GPIO1-Pad46)") (class "Default")
      (node (ref "T") (pin "46") (pinfunction "GPIO1_46") (pintype "bidirectional"))
    )
    (net (code "213") (name "unconnected-(TD-GPIO2-Pad45)") (class "Default")
      (node (ref "T") (pin "45") (pinfunction "GPIO2_45") (pintype "bidirectional"))
    )
    (net (code "214") (name "unconnected-(TD-GPIO3-Pad44)") (class "Default")
      (node (ref "T") (pin "44") (pinfunction "GPIO3_44") (pintype "bidirectional"))
    )
    (net (code "215") (name "unconnected-(TD-GPIO4-Pad43)") (class "Default")
      (node (ref "T") (pin "43") (pinfunction "GPIO4_43") (pintype "bidirectional"))
    )
    (net (code "216") (name "unconnected-(TD-GPIO5-Pad42)") (class "Default")
      (node (ref "T") (pin "42") (pinfunction "GPIO5_42") (pintype "bidirectional"))
    )
    (net (code "217") (name "unconnected-(TE-NC1-Pad36)") (class "Default")
      (node (ref "T") (pin "36") (pinfunction "NC1_36") (pintype "bidirectional"))
    )
    (net (code "218") (name "unconnected-(TE-NC2-Pad75)") (class "Default")
      (node (ref "T") (pin "75") (pinfunction "NC2_75") (pintype "bidirectional"))
    )
    (net (code "219") (name "unconnected-(U$3-Pad$P3)") (class "Default")
      (node (ref "U$3") (pin "$P3") (pinfunction "$P3_$P3") (pintype "passive"))
    )
    (net (code "220") (name "unconnected-(U$3-Pad$P10)") (class "Default")
      (node (ref "U$3") (pin "$P10") (pinfunction "$P10_$P10") (pintype "passive"))
    )
    (net (code "221") (name "unconnected-(U$5-5-PadP$5)") (class "Default")
      (node (ref "U$5") (pin "P$5") (pinfunction "5_P$5") (pintype "bidirectional"))
    )
    (net (code "222") (name "unconnected-(U$5-6-PadP$6)") (class "Default")
      (node (ref "U$5") (pin "P$6") (pinfunction "6_P$6") (pintype "bidirectional"))
    )
  )
)
